# sortirovka.net
KiCad netlist of a schematic drawn in EAGLE
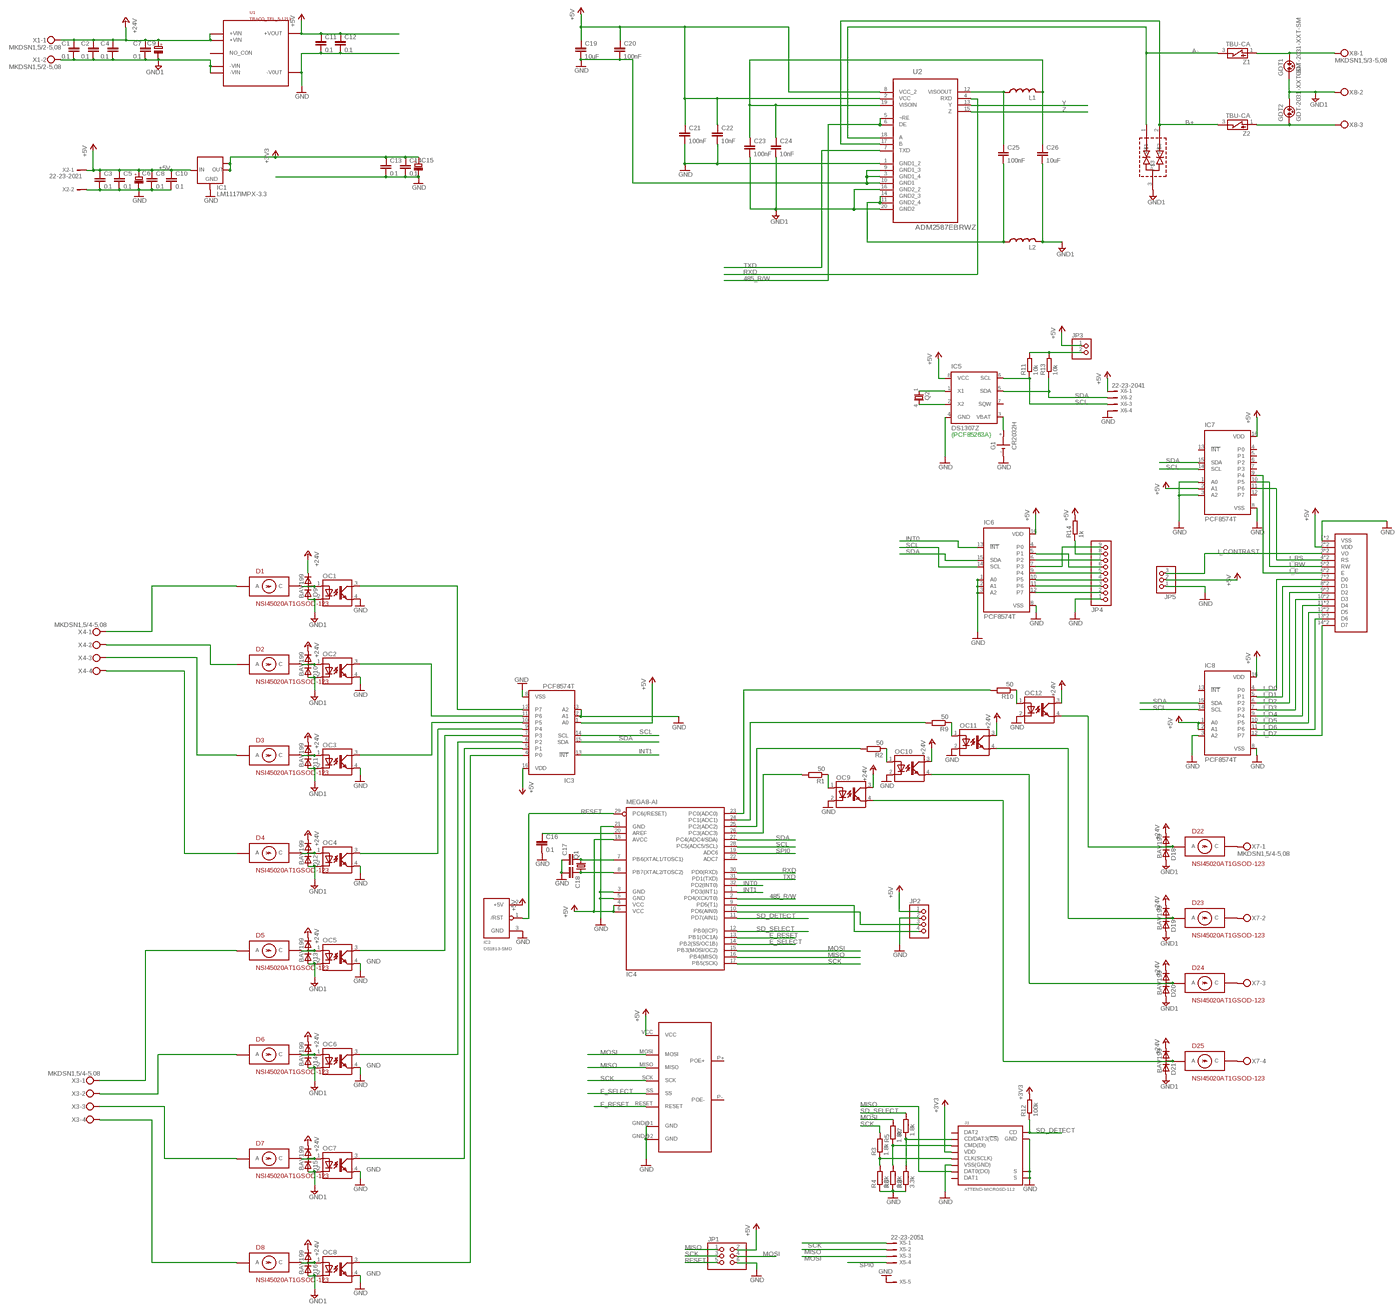
[diagram p0: schematic, sheet 1, overview]
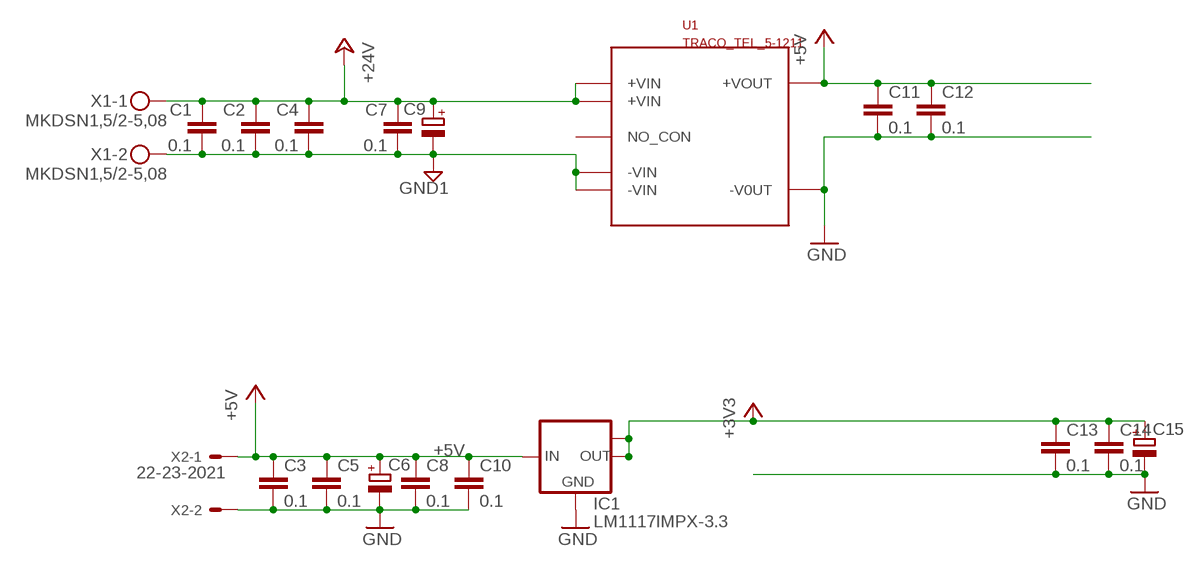
[diagram p1: schematic, sheet 1, part 1 of 4]
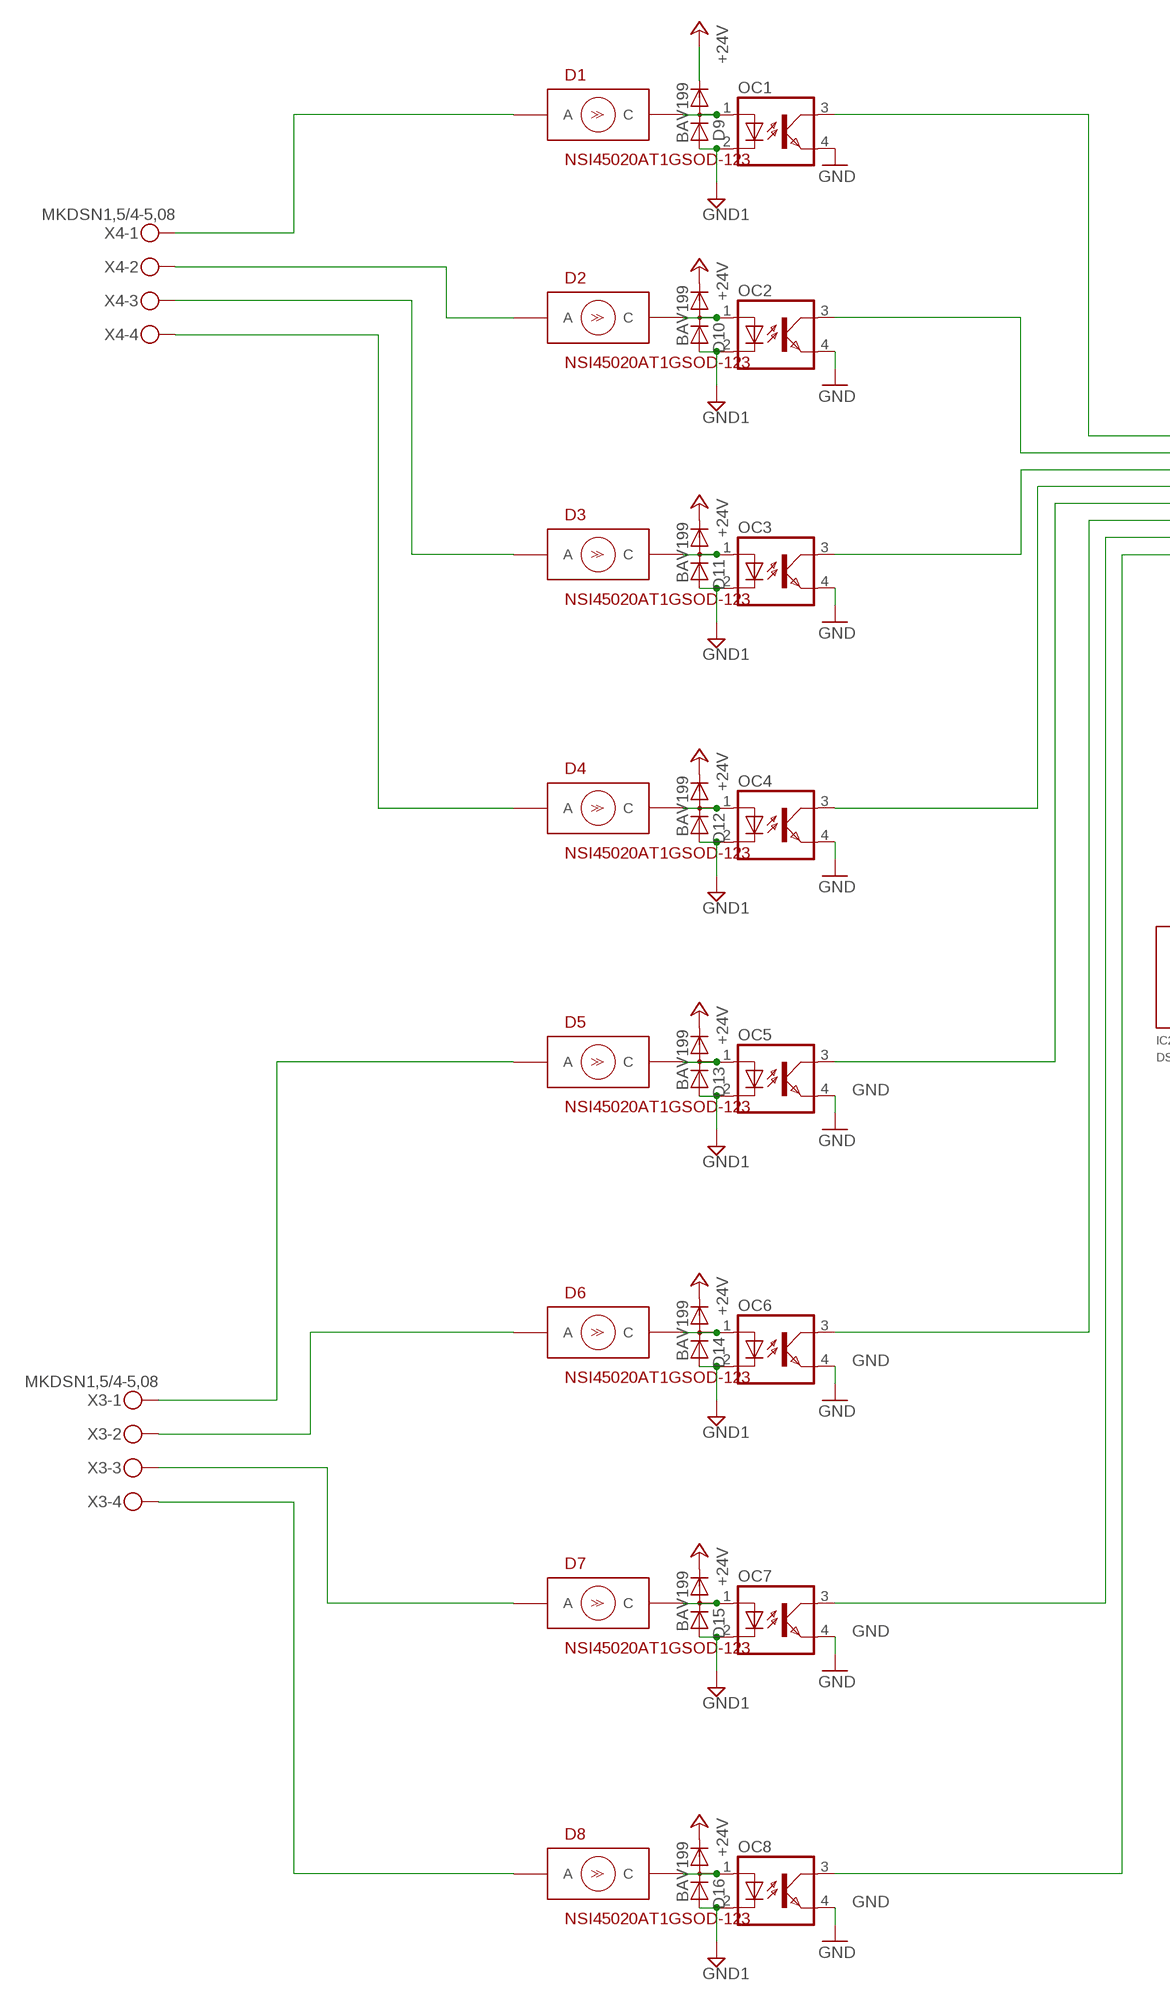
[diagram p2: schematic, sheet 1, part 2 of 4]
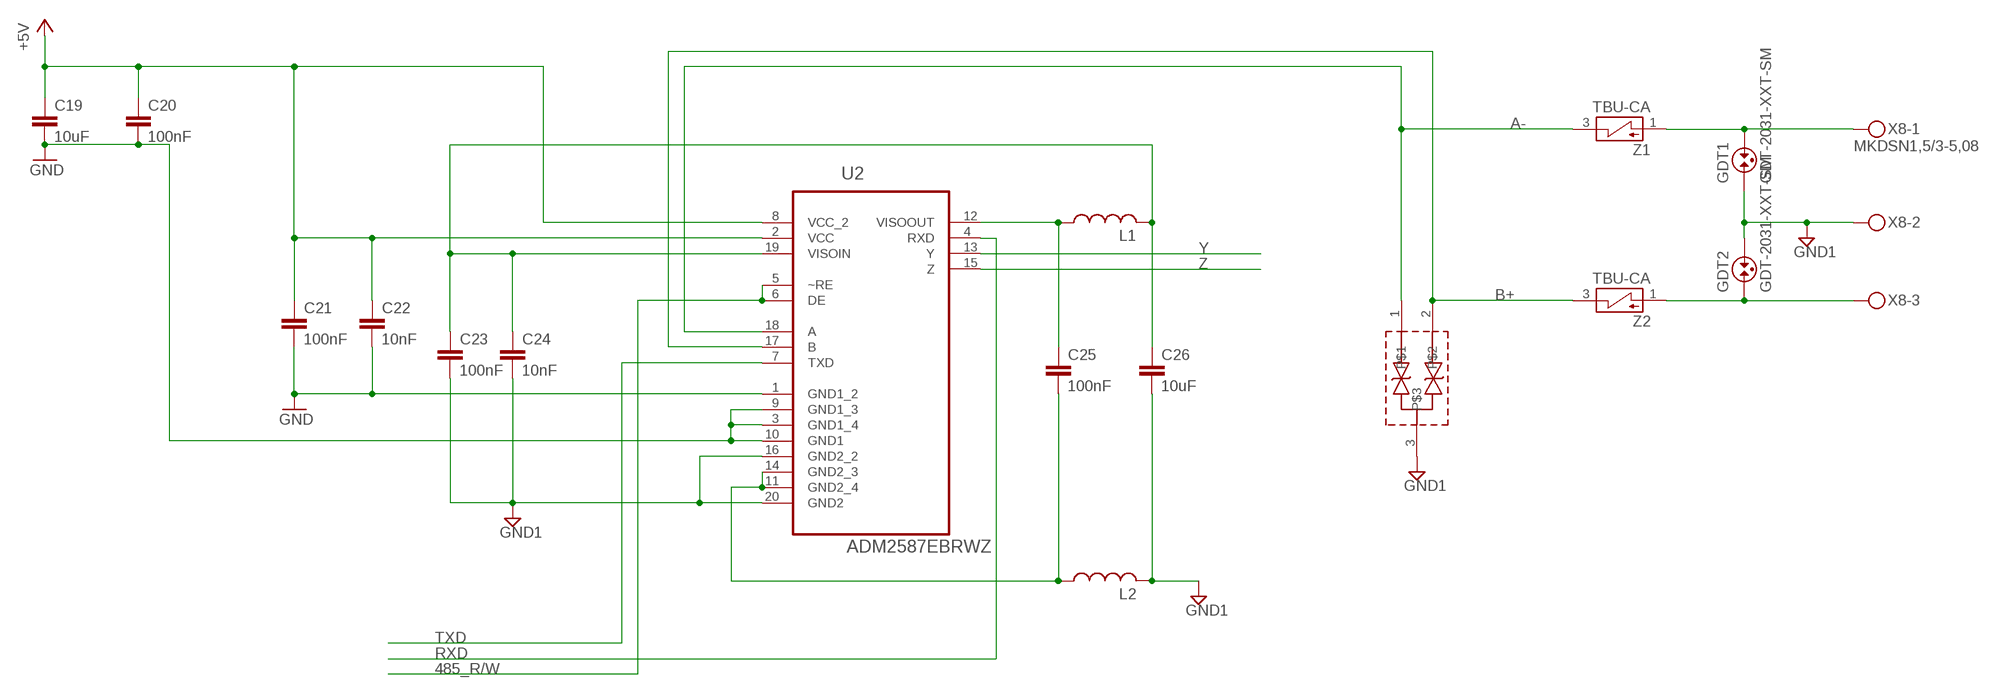
[diagram p3: schematic, sheet 1, part 3 of 4]
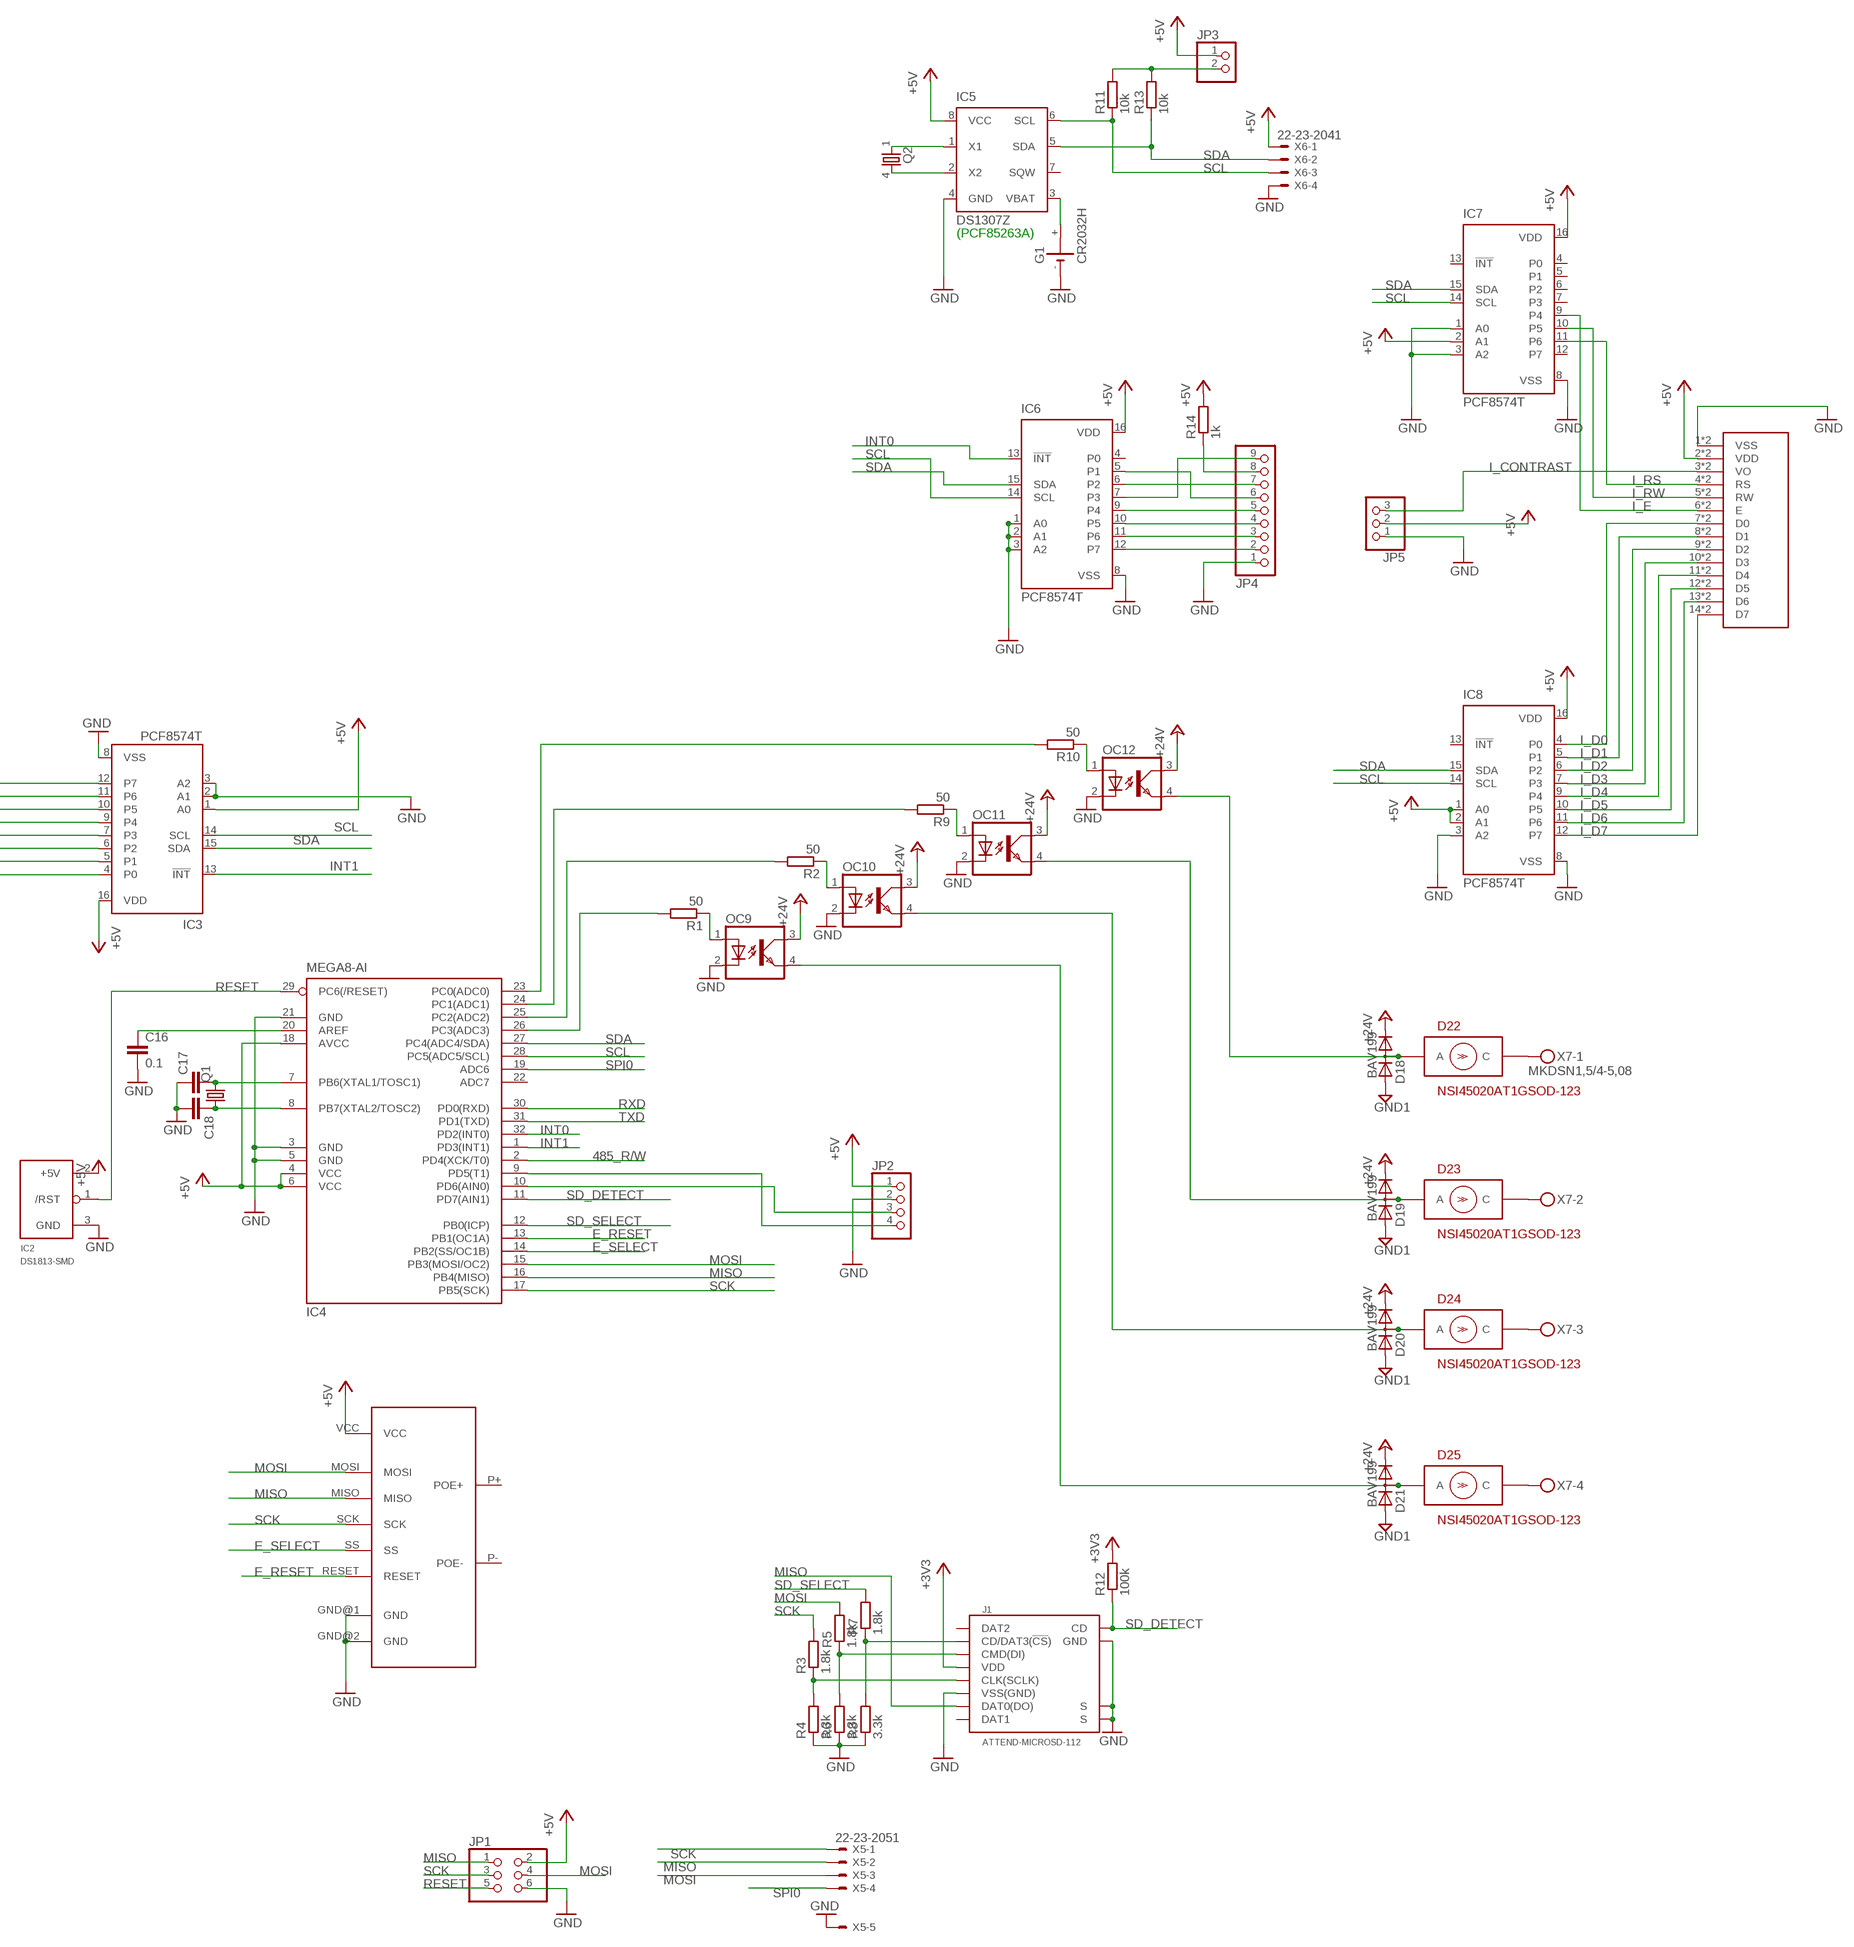
[diagram p4: schematic, sheet 1, part 4 of 4]

(export (version "E")
  (design (tool "Eeschema 10.0.6"))
  (components
    (comp (ref "C1")
      (value "0.1")
      (footprint "eagle-import:C0805")
      (libsource (lib "eagle-import") (part "C-EUC0805"))
    )
    (comp (ref "C2")
      (value "0.1")
      (footprint "eagle-import:C0805")
      (libsource (lib "eagle-import") (part "C-EUC0805"))
    )
    (comp (ref "C3")
      (value "0.1")
      (footprint "eagle-import:C0805")
      (libsource (lib "eagle-import") (part "C-EUC0805"))
    )
    (comp (ref "C4")
      (value "0.1")
      (footprint "eagle-import:C0805")
      (libsource (lib "eagle-import") (part "C-EUC0805"))
    )
    (comp (ref "C5")
      (value "0.1")
      (footprint "eagle-import:C0805")
      (libsource (lib "eagle-import") (part "C-EUC0805"))
    )
    (comp (ref "C6")
      (value "CPOL-EU153CLV-0605")
      (footprint "eagle-import:153CLV-0605")
      (libsource (lib "eagle-import") (part "CPOL-EU153CLV-0605"))
    )
    (comp (ref "C7")
      (value "0.1")
      (footprint "eagle-import:C0805")
      (libsource (lib "eagle-import") (part "C-EUC0805"))
    )
    (comp (ref "C8")
      (value "0.1")
      (footprint "eagle-import:C0805")
      (libsource (lib "eagle-import") (part "C-EUC0805"))
    )
    (comp (ref "C9")
      (value "CPOL-EU153CLV-0605")
      (footprint "eagle-import:153CLV-0605")
      (libsource (lib "eagle-import") (part "CPOL-EU153CLV-0605"))
    )
    (comp (ref "C10")
      (value "0.1")
      (footprint "eagle-import:C0805")
      (libsource (lib "eagle-import") (part "C-EUC0805"))
    )
    (comp (ref "C11")
      (value "0.1")
      (footprint "eagle-import:C0805")
      (libsource (lib "eagle-import") (part "C-EUC0805"))
    )
    (comp (ref "C12")
      (value "0.1")
      (footprint "eagle-import:C0805")
      (libsource (lib "eagle-import") (part "C-EUC0805"))
    )
    (comp (ref "C13")
      (value "0.1")
      (footprint "eagle-import:C0805")
      (libsource (lib "eagle-import") (part "C-EUC0805"))
    )
    (comp (ref "C14")
      (value "0.1")
      (footprint "eagle-import:C0805")
      (libsource (lib "eagle-import") (part "C-EUC0805"))
    )
    (comp (ref "C15")
      (value "CPOL-EU153CLV-0605")
      (footprint "eagle-import:153CLV-0605")
      (libsource (lib "eagle-import") (part "CPOL-EU153CLV-0605"))
    )
    (comp (ref "C16")
      (value "0.1")
      (footprint "eagle-import:C0805")
      (libsource (lib "eagle-import") (part "C-EUC0805"))
    )
    (comp (ref "C17")
      (value "C-EUC0805")
      (footprint "eagle-import:C0805")
      (libsource (lib "eagle-import") (part "C-EUC0805"))
    )
    (comp (ref "C18")
      (value "C-EUC0805")
      (footprint "eagle-import:C0805")
      (libsource (lib "eagle-import") (part "C-EUC0805"))
    )
    (comp (ref "C19")
      (value "10uF")
      (footprint "eagle-import:C0805")
      (libsource (lib "eagle-import") (part "C-EUC0805"))
    )
    (comp (ref "C20")
      (value "100nF")
      (footprint "eagle-import:C0805")
      (libsource (lib "eagle-import") (part "C-EUC0805"))
    )
    (comp (ref "C21")
      (value "100nF")
      (footprint "eagle-import:C0805")
      (libsource (lib "eagle-import") (part "C-EUC0805"))
    )
    (comp (ref "C22")
      (value "10nF")
      (footprint "eagle-import:C0805")
      (libsource (lib "eagle-import") (part "C-EUC0805"))
    )
    (comp (ref "C23")
      (value "100nF")
      (footprint "eagle-import:C0805")
      (libsource (lib "eagle-import") (part "C-EUC0805"))
    )
    (comp (ref "C24")
      (value "10nF")
      (footprint "eagle-import:C0805")
      (libsource (lib "eagle-import") (part "C-EUC0805"))
    )
    (comp (ref "C25")
      (value "100nF")
      (footprint "eagle-import:C0805")
      (libsource (lib "eagle-import") (part "C-EUC0805"))
    )
    (comp (ref "C26")
      (value "10uF")
      (footprint "eagle-import:C0805")
      (libsource (lib "eagle-import") (part "C-EUC0805"))
    )
    (comp (ref "D1")
      (value "NSI45020AT1GSOD-123")
      (footprint "eagle-import:SOD123")
      (libsource (lib "eagle-import") (part "NSI45020AT1GSOD-123"))
    )
    (comp (ref "D2")
      (value "NSI45020AT1GSOD-123")
      (footprint "eagle-import:SOD123")
      (libsource (lib "eagle-import") (part "NSI45020AT1GSOD-123"))
    )
    (comp (ref "D3")
      (value "NSI45020AT1GSOD-123")
      (footprint "eagle-import:SOD123")
      (libsource (lib "eagle-import") (part "NSI45020AT1GSOD-123"))
    )
    (comp (ref "D4")
      (value "NSI45020AT1GSOD-123")
      (footprint "eagle-import:SOD123")
      (libsource (lib "eagle-import") (part "NSI45020AT1GSOD-123"))
    )
    (comp (ref "D5")
      (value "NSI45020AT1GSOD-123")
      (footprint "eagle-import:SOD123")
      (libsource (lib "eagle-import") (part "NSI45020AT1GSOD-123"))
    )
    (comp (ref "D6")
      (value "NSI45020AT1GSOD-123")
      (footprint "eagle-import:SOD123")
      (libsource (lib "eagle-import") (part "NSI45020AT1GSOD-123"))
    )
    (comp (ref "D7")
      (value "NSI45020AT1GSOD-123")
      (footprint "eagle-import:SOD123")
      (libsource (lib "eagle-import") (part "NSI45020AT1GSOD-123"))
    )
    (comp (ref "D8")
      (value "NSI45020AT1GSOD-123")
      (footprint "eagle-import:SOD123")
      (libsource (lib "eagle-import") (part "NSI45020AT1GSOD-123"))
    )
    (comp (ref "D9")
      (value "BAV199")
      (footprint "eagle-import:SOT23")
      (libsource (lib "eagle-import") (part "BAV199"))
    )
    (comp (ref "D10")
      (value "BAV199")
      (footprint "eagle-import:SOT23")
      (libsource (lib "eagle-import") (part "BAV199"))
    )
    (comp (ref "D11")
      (value "BAV199")
      (footprint "eagle-import:SOT23")
      (libsource (lib "eagle-import") (part "BAV199"))
    )
    (comp (ref "D12")
      (value "BAV199")
      (footprint "eagle-import:SOT23")
      (libsource (lib "eagle-import") (part "BAV199"))
    )
    (comp (ref "D13")
      (value "BAV199")
      (footprint "eagle-import:SOT23")
      (libsource (lib "eagle-import") (part "BAV199"))
    )
    (comp (ref "D14")
      (value "BAV199")
      (footprint "eagle-import:SOT23")
      (libsource (lib "eagle-import") (part "BAV199"))
    )
    (comp (ref "D15")
      (value "BAV199")
      (footprint "eagle-import:SOT23")
      (libsource (lib "eagle-import") (part "BAV199"))
    )
    (comp (ref "D16")
      (value "BAV199")
      (footprint "eagle-import:SOT23")
      (libsource (lib "eagle-import") (part "BAV199"))
    )
    (comp (ref "D17")
      (value "CDSOT23-SM712SOT23-R")
      (footprint "eagle-import:SOT23-R")
      (libsource (lib "eagle-import") (part "CDSOT23-SM712SOT23-R"))
    )
    (comp (ref "D18")
      (value "BAV199")
      (footprint "eagle-import:SOT23")
      (libsource (lib "eagle-import") (part "BAV199"))
    )
    (comp (ref "D19")
      (value "BAV199")
      (footprint "eagle-import:SOT23")
      (libsource (lib "eagle-import") (part "BAV199"))
    )
    (comp (ref "D20")
      (value "BAV199")
      (footprint "eagle-import:SOT23")
      (libsource (lib "eagle-import") (part "BAV199"))
    )
    (comp (ref "D21")
      (value "BAV199")
      (footprint "eagle-import:SOT23")
      (libsource (lib "eagle-import") (part "BAV199"))
    )
    (comp (ref "D22")
      (value "NSI45020AT1GSOD-123")
      (footprint "eagle-import:SOD123")
      (libsource (lib "eagle-import") (part "NSI45020AT1GSOD-123"))
    )
    (comp (ref "D23")
      (value "NSI45020AT1GSOD-123")
      (footprint "eagle-import:SOD123")
      (libsource (lib "eagle-import") (part "NSI45020AT1GSOD-123"))
    )
    (comp (ref "D24")
      (value "NSI45020AT1GSOD-123")
      (footprint "eagle-import:SOD123")
      (libsource (lib "eagle-import") (part "NSI45020AT1GSOD-123"))
    )
    (comp (ref "D25")
      (value "NSI45020AT1GSOD-123")
      (footprint "eagle-import:SOD123")
      (libsource (lib "eagle-import") (part "NSI45020AT1GSOD-123"))
    )
    (comp (ref "G1")
      (value "CR2032H")
      (footprint "eagle-import:CR2032H")
      (libsource (lib "eagle-import") (part "CR2032H"))
    )
    (comp (ref "GDT1")
      (value "GDT-2031-XXT-SM")
      (footprint "eagle-import:2031-XXT-SM")
      (libsource (lib "eagle-import") (part "GDT-2031-XXT-SM"))
    )
    (comp (ref "GDT2")
      (value "GDT-2031-XXT-SM")
      (footprint "eagle-import:2031-XXT-SM")
      (libsource (lib "eagle-import") (part "GDT-2031-XXT-SM"))
    )
    (comp (ref "IC1")
      (value "LM1117IMPX-3.3")
      (footprint "eagle-import:SOT223")
      (libsource (lib "eagle-import") (part "LM1117IMPX-3.3"))
    )
    (comp (ref "IC2")
      (value "DS1813-SMD")
      (footprint "eagle-import:SOT-23")
      (libsource (lib "eagle-import") (part "DS1813-SMD"))
    )
    (comp (ref "IC3")
      (value "PCF8574T")
      (footprint "eagle-import:SO16W")
      (fields (field (name "MPN") "PCF8574T/3,512"))
      (libsource (lib "eagle-import") (part "PCF8574T"))
    )
    (comp (ref "IC4")
      (value "MEGA8-AI")
      (footprint "eagle-import:TQFP32-08")
      (fields (field (name "MPN") "ATMEGA8-16AU"))
      (libsource (lib "eagle-import") (part "MEGA8-AI"))
    )
    (comp (ref "IC5")
      (value "DS1307Z")
      (footprint "eagle-import:SOIC8")
      (libsource (lib "eagle-import") (part "DS1307Z"))
    )
    (comp (ref "IC6")
      (value "PCF8574T")
      (footprint "eagle-import:SO16W")
      (fields (field (name "MPN") "PCF8574T/3,512"))
      (libsource (lib "eagle-import") (part "PCF8574T"))
    )
    (comp (ref "IC7")
      (value "PCF8574T")
      (footprint "eagle-import:SO16W")
      (fields (field (name "MPN") "PCF8574T/3,512"))
      (libsource (lib "eagle-import") (part "PCF8574T"))
    )
    (comp (ref "IC8")
      (value "PCF8574T")
      (footprint "eagle-import:SO16W")
      (fields (field (name "MPN") "PCF8574T/3,512"))
      (libsource (lib "eagle-import") (part "PCF8574T"))
    )
    (comp (ref "J1")
      (value "ATTEND-MICROSD-112")
      (footprint "eagle-import:ATTEND-112")
      (libsource (lib "eagle-import") (part "ATTEND-MICROSD-112"))
    )
    (comp (ref "JP1")
      (value "PINHD-2X3")
      (footprint "eagle-import:2X03")
      (libsource (lib "eagle-import") (part "PINHD-2X3"))
    )
    (comp (ref "JP2")
      (value "PINHD-1X4")
      (footprint "eagle-import:1X04")
      (libsource (lib "eagle-import") (part "PINHD-1X4"))
    )
    (comp (ref "JP3")
      (value "PINHD-1X2")
      (footprint "eagle-import:1X02")
      (libsource (lib "eagle-import") (part "PINHD-1X2"))
    )
    (comp (ref "JP4")
      (value "PINHD-1X9")
      (footprint "eagle-import:1X09")
      (libsource (lib "eagle-import") (part "PINHD-1X9"))
    )
    (comp (ref "JP5")
      (value "PINHD-1X3")
      (footprint "eagle-import:1X03")
      (libsource (lib "eagle-import") (part "PINHD-1X3"))
    )
    (comp (ref "L1")
      (value "L-US0402")
      (footprint "eagle-import:L0402")
      (libsource (lib "eagle-import") (part "L-US0402"))
    )
    (comp (ref "L2")
      (value "L-US0402")
      (footprint "eagle-import:L0402")
      (libsource (lib "eagle-import") (part "L-US0402"))
    )
    (comp (ref "LCD1")
      (value "2X16LCDBOTHM162SD07")
      (footprint "eagle-import:2X16LCDBOTH-1")
      (libsource (lib "eagle-import") (part "2X16LCDBOTHM162SD07"))
    )
    (comp (ref "MOD1")
      (value "W5100_MODULESMALL")
      (footprint "eagle-import:W5100_MODULE_1")
      (libsource (lib "eagle-import") (part "W5100_MODULESMALL"))
    )
    (comp (ref "OC1")
      (value "SFH6106REAL")
      (footprint "eagle-import:SFH6106")
      (libsource (lib "eagle-import") (part "SFH6106REAL"))
    )
    (comp (ref "OC2")
      (value "SFH6106REAL")
      (footprint "eagle-import:SFH6106")
      (libsource (lib "eagle-import") (part "SFH6106REAL"))
    )
    (comp (ref "OC3")
      (value "SFH6106REAL")
      (footprint "eagle-import:SFH6106")
      (libsource (lib "eagle-import") (part "SFH6106REAL"))
    )
    (comp (ref "OC4")
      (value "SFH6106REAL")
      (footprint "eagle-import:SFH6106")
      (libsource (lib "eagle-import") (part "SFH6106REAL"))
    )
    (comp (ref "OC5")
      (value "SFH6106REAL")
      (footprint "eagle-import:SFH6106")
      (libsource (lib "eagle-import") (part "SFH6106REAL"))
    )
    (comp (ref "OC6")
      (value "SFH6106REAL")
      (footprint "eagle-import:SFH6106")
      (libsource (lib "eagle-import") (part "SFH6106REAL"))
    )
    (comp (ref "OC7")
      (value "SFH6106REAL")
      (footprint "eagle-import:SFH6106")
      (libsource (lib "eagle-import") (part "SFH6106REAL"))
    )
    (comp (ref "OC8")
      (value "SFH6106REAL")
      (footprint "eagle-import:SFH6106")
      (libsource (lib "eagle-import") (part "SFH6106REAL"))
    )
    (comp (ref "OC9")
      (value "SFH6106REAL")
      (footprint "eagle-import:SFH6106")
      (libsource (lib "eagle-import") (part "SFH6106REAL"))
    )
    (comp (ref "OC10")
      (value "SFH6106REAL")
      (footprint "eagle-import:SFH6106")
      (libsource (lib "eagle-import") (part "SFH6106REAL"))
    )
    (comp (ref "OC11")
      (value "SFH6106REAL")
      (footprint "eagle-import:SFH6106")
      (libsource (lib "eagle-import") (part "SFH6106REAL"))
    )
    (comp (ref "OC12")
      (value "SFH6106REAL")
      (footprint "eagle-import:SFH6106")
      (libsource (lib "eagle-import") (part "SFH6106REAL"))
    )
    (comp (ref "Q1")
      (value "CRYSTALSM49")
      (footprint "eagle-import:SM49")
      (libsource (lib "eagle-import") (part "CRYSTALSM49"))
    )
    (comp (ref "Q2")
      (value "MA306")
      (footprint "eagle-import:MA306")
      (libsource (lib "eagle-import") (part "MA306"))
    )
    (comp (ref "R1")
      (value "50")
      (footprint "eagle-import:R0805")
      (libsource (lib "eagle-import") (part "R-EU_R0805"))
    )
    (comp (ref "R2")
      (value "50")
      (footprint "eagle-import:R0805")
      (libsource (lib "eagle-import") (part "R-EU_R0805"))
    )
    (comp (ref "R3")
      (value "1.8k")
      (footprint "eagle-import:M0805")
      (libsource (lib "eagle-import") (part "R-EU_M0805"))
    )
    (comp (ref "R4")
      (value "3.3k")
      (footprint "eagle-import:M0805")
      (libsource (lib "eagle-import") (part "R-EU_M0805"))
    )
    (comp (ref "R5")
      (value "1.8k")
      (footprint "eagle-import:M0805")
      (libsource (lib "eagle-import") (part "R-EU_M0805"))
    )
    (comp (ref "R6")
      (value "3.3k")
      (footprint "eagle-import:M0805")
      (libsource (lib "eagle-import") (part "R-EU_M0805"))
    )
    (comp (ref "R7")
      (value "1.8k")
      (footprint "eagle-import:M0805")
      (libsource (lib "eagle-import") (part "R-EU_M0805"))
    )
    (comp (ref "R8")
      (value "3.3k")
      (footprint "eagle-import:M0805")
      (libsource (lib "eagle-import") (part "R-EU_M0805"))
    )
    (comp (ref "R9")
      (value "50")
      (footprint "eagle-import:R0805")
      (libsource (lib "eagle-import") (part "R-EU_R0805"))
    )
    (comp (ref "R10")
      (value "50")
      (footprint "eagle-import:R0805")
      (libsource (lib "eagle-import") (part "R-EU_R0805"))
    )
    (comp (ref "R11")
      (value "10k")
      (footprint "eagle-import:R0805")
      (libsource (lib "eagle-import") (part "R-EU_R0805"))
    )
    (comp (ref "R12")
      (value "100k")
      (footprint "eagle-import:M0805")
      (libsource (lib "eagle-import") (part "R-EU_M0805"))
    )
    (comp (ref "R13")
      (value "10k")
      (footprint "eagle-import:R0805")
      (libsource (lib "eagle-import") (part "R-EU_R0805"))
    )
    (comp (ref "R14")
      (value "1k")
      (footprint "eagle-import:R0805")
      (libsource (lib "eagle-import") (part "R-EU_R0805"))
    )
    (comp (ref "U1")
      (value "TRACO_TEL_5-1211")
      (footprint "eagle-import:TRACO_POWER_TL5")
      (libsource (lib "eagle-import") (part "TRACO_TEL_5-1211"))
    )
    (comp (ref "U2")
      (value "ADM2587EBRWZ")
      (footprint "eagle-import:SOIC127P1032X265-20N")
      (libsource (lib "eagle-import") (part "ADM2587EBRWZ"))
    )
    (comp (ref "X1")
      (value "MKDSN1,5/2-5,08")
      (footprint "eagle-import:MKDSN1,5_2-5,08")
      (libsource (lib "eagle-import") (part "MKDSN1,5/2-5,08"))
    )
    (comp (ref "X2")
      (value "22-23-2021")
      (footprint "eagle-import:22-23-2021")
      (fields (field (name "MF") "MOLEX"))
      (libsource (lib "eagle-import") (part "22-23-2021"))
    )
    (comp (ref "X3")
      (value "MKDSN1,5/4-5,08")
      (footprint "eagle-import:MKDSN1,5_4-5,08")
      (libsource (lib "eagle-import") (part "MKDSN1,5/4-5,08"))
    )
    (comp (ref "X4")
      (value "MKDSN1,5/4-5,08")
      (footprint "eagle-import:MKDSN1,5_4-5,08")
      (libsource (lib "eagle-import") (part "MKDSN1,5/4-5,08"))
    )
    (comp (ref "X5")
      (value "22-23-2051")
      (footprint "eagle-import:22-23-2051")
      (fields (field (name "MF") "MOLEX"))
      (libsource (lib "eagle-import") (part "22-23-2051"))
    )
    (comp (ref "X6")
      (value "22-23-2041")
      (footprint "eagle-import:22-23-2041")
      (fields (field (name "MF") "MOLEX"))
      (libsource (lib "eagle-import") (part "22-23-2041"))
    )
    (comp (ref "X7")
      (value "MKDSN1,5/4-5,08")
      (footprint "eagle-import:MKDSN1,5_4-5,08")
      (libsource (lib "eagle-import") (part "MKDSN1,5/4-5,08"))
    )
    (comp (ref "X8")
      (value "MKDSN1,5/3-5,08")
      (footprint "eagle-import:MKDSN1,5_3-5,08")
      (libsource (lib "eagle-import") (part "MKDSN1,5/3-5,08"))
    )
    (comp (ref "Z1")
      (value "TBU-CA")
      (footprint "eagle-import:TBU-CA")
      (libsource (lib "eagle-import") (part "TBU-CA"))
    )
    (comp (ref "Z2")
      (value "TBU-CA")
      (footprint "eagle-import:TBU-CA")
      (libsource (lib "eagle-import") (part "TBU-CA"))
    )
  )
  (nets
    (net (code "1") (name "+3V3") (class "Default")
      (node (ref "C13") (pin "1") (pinfunction "1_1") (pintype "passive"))
      (node (ref "C14") (pin "1") (pinfunction "1_1") (pintype "passive"))
      (node (ref "C15") (pin "+") (pinfunction "+_+") (pintype "passive"))
      (node (ref "IC1") (pin "2") (pinfunction "OUT_2") (pintype "passive"))
      (node (ref "IC1") (pin "TAB") (pinfunction "OUT1_TAB") (pintype "passive"))
      (node (ref "J1") (pin "VDD") (pinfunction "VDD_VDD") (pintype "power_in"))
      (node (ref "R12") (pin "2") (pinfunction "2_2") (pintype "passive"))
    )
    (net (code "2") (name "+5V") (class "Default")
      (node (ref "C10") (pin "1") (pinfunction "1_1") (pintype "passive"))
      (node (ref "C11") (pin "1") (pinfunction "1_1") (pintype "passive"))
      (node (ref "C12") (pin "1") (pinfunction "1_1") (pintype "passive"))
      (node (ref "C19") (pin "1") (pinfunction "1_1") (pintype "passive"))
      (node (ref "C20") (pin "1") (pinfunction "1_1") (pintype "passive"))
      (node (ref "C21") (pin "1") (pinfunction "1_1") (pintype "passive"))
      (node (ref "C22") (pin "1") (pinfunction "1_1") (pintype "passive"))
      (node (ref "C3") (pin "1") (pinfunction "1_1") (pintype "passive"))
      (node (ref "C5") (pin "1") (pinfunction "1_1") (pintype "passive"))
      (node (ref "C6") (pin "+") (pinfunction "+_+") (pintype "passive"))
      (node (ref "C8") (pin "1") (pinfunction "1_1") (pintype "passive"))
      (node (ref "IC1") (pin "3") (pinfunction "IN_3") (pintype "input"))
      (node (ref "IC2") (pin "2") (pinfunction "+5V_2") (pintype "power_in"))
      (node (ref "IC3") (pin "1") (pinfunction "A0_1") (pintype "input"))
      (node (ref "IC3") (pin "16") (pinfunction "VDD_16") (pintype "power_in"))
      (node (ref "IC4") (pin "18") (pinfunction "AVCC_18") (pintype "power_in"))
      (node (ref "IC4") (pin "4") (pinfunction "VCC_4") (pintype "power_in"))
      (node (ref "IC4") (pin "6") (pinfunction "VCC_6") (pintype "power_in"))
      (node (ref "IC5") (pin "8") (pinfunction "VCC_8") (pintype "power_in"))
      (node (ref "IC6") (pin "16") (pinfunction "VDD_16") (pintype "power_in"))
      (node (ref "IC7") (pin "16") (pinfunction "VDD_16") (pintype "power_in"))
      (node (ref "IC7") (pin "2") (pinfunction "A1_2") (pintype "input"))
      (node (ref "IC8") (pin "1") (pinfunction "A0_1") (pintype "input"))
      (node (ref "IC8") (pin "16") (pinfunction "VDD_16") (pintype "power_in"))
      (node (ref "IC8") (pin "2") (pinfunction "A1_2") (pintype "input"))
      (node (ref "JP1") (pin "2") (pinfunction "2_2") (pintype "passive"))
      (node (ref "JP2") (pin "1") (pinfunction "1_1") (pintype "passive"))
      (node (ref "JP3") (pin "1") (pinfunction "1_1") (pintype "passive"))
      (node (ref "JP5") (pin "2") (pinfunction "2_2") (pintype "passive"))
      (node (ref "LCD1") (pin "16") (pinfunction "VDD_16") (pintype "bidirectional"))
      (node (ref "LCD1") (pin "2") (pinfunction "VDD_2") (pintype "bidirectional"))
      (node (ref "MOD1") (pin "VCC") (pinfunction "VCC_VCC") (pintype "bidirectional"))
      (node (ref "R14") (pin "2") (pinfunction "2_2") (pintype "passive"))
      (node (ref "U1") (pin "+VOUT") (pinfunction "+VOUT_+VOUT") (pintype "bidirectional"))
      (node (ref "U2") (pin "2") (pinfunction "VCC_2") (pintype "power_in"))
      (node (ref "U2") (pin "8") (pinfunction "VCC_2_8") (pintype "power_in"))
      (node (ref "X2") (pin "1") (pinfunction "S_1") (pintype "passive"))
      (node (ref "X6") (pin "1") (pinfunction "S_1") (pintype "passive"))
    )
    (net (code "3") (name "+24V") (class "Default")
      (node (ref "C1") (pin "1") (pinfunction "1_1") (pintype "passive"))
      (node (ref "C2") (pin "1") (pinfunction "1_1") (pintype "passive"))
      (node (ref "C4") (pin "1") (pinfunction "1_1") (pintype "passive"))
      (node (ref "C7") (pin "1") (pinfunction "1_1") (pintype "passive"))
      (node (ref "C9") (pin "+") (pinfunction "+_+") (pintype "passive"))
      (node (ref "D10") (pin "2") (pinfunction "C_2") (pintype "passive"))
      (node (ref "D11") (pin "2") (pinfunction "C_2") (pintype "passive"))
      (node (ref "D12") (pin "2") (pinfunction "C_2") (pintype "passive"))
      (node (ref "D13") (pin "2") (pinfunction "C_2") (pintype "passive"))
      (node (ref "D14") (pin "2") (pinfunction "C_2") (pintype "passive"))
      (node (ref "D15") (pin "2") (pinfunction "C_2") (pintype "passive"))
      (node (ref "D16") (pin "2") (pinfunction "C_2") (pintype "passive"))
      (node (ref "D18") (pin "2") (pinfunction "C_2") (pintype "passive"))
      (node (ref "D19") (pin "2") (pinfunction "C_2") (pintype "passive"))
      (node (ref "D20") (pin "2") (pinfunction "C_2") (pintype "passive"))
      (node (ref "D21") (pin "2") (pinfunction "C_2") (pintype "passive"))
      (node (ref "D9") (pin "2") (pinfunction "C_2") (pintype "passive"))
      (node (ref "OC10") (pin "3") (pinfunction "COL_3") (pintype "passive"))
      (node (ref "OC11") (pin "3") (pinfunction "COL_3") (pintype "passive"))
      (node (ref "OC12") (pin "3") (pinfunction "COL_3") (pintype "passive"))
      (node (ref "OC9") (pin "3") (pinfunction "COL_3") (pintype "passive"))
      (node (ref "U1") (pin "+VIN@1") (pinfunction "+VIN_+VIN@1") (pintype "bidirectional"))
      (node (ref "U1") (pin "+VIN@2") (pinfunction "+VIN_+VIN@2") (pintype "bidirectional"))
      (node (ref "X1") (pin "1") (pinfunction "KL_1") (pintype "passive"))
    )
    (net (code "4") (name "/485_R{slash}W") (class "Default")
      (node (ref "IC4") (pin "2") (pinfunction "PD4(XCK/T0)_2") (pintype "bidirectional"))
      (node (ref "U2") (pin "5") (pinfunction "~{RE}_5") (pintype "input"))
      (node (ref "U2") (pin "6") (pinfunction "DE_6") (pintype "input"))
    )
    (net (code "5") (name "/A-") (class "Default")
      (node (ref "D17") (pin "1") (pinfunction "P$1_1") (pintype "bidirectional"))
      (node (ref "U2") (pin "18") (pinfunction "A_18") (pintype "input"))
      (node (ref "Z1") (pin "3") (pinfunction "2_3") (pintype "passive"))
    )
    (net (code "6") (name "/B+") (class "Default")
      (node (ref "D17") (pin "2") (pinfunction "P$2_2") (pintype "bidirectional"))
      (node (ref "U2") (pin "17") (pinfunction "B_17") (pintype "input"))
      (node (ref "Z2") (pin "3") (pinfunction "2_3") (pintype "passive"))
    )
    (net (code "7") (name "/E_RESET") (class "Default")
      (node (ref "IC4") (pin "13") (pinfunction "PB1(OC1A)_13") (pintype "bidirectional"))
      (node (ref "MOD1") (pin "RESET") (pinfunction "RESET_RESET") (pintype "bidirectional"))
    )
    (net (code "8") (name "/E_SELECT") (class "Default")
      (node (ref "IC4") (pin "14") (pinfunction "PB2(SS/OC1B)_14") (pintype "bidirectional"))
      (node (ref "MOD1") (pin "SS") (pinfunction "SS_SS") (pintype "bidirectional"))
    )
    (net (code "9") (name "/INT0") (class "Default")
      (node (ref "IC4") (pin "32") (pinfunction "PD2(INT0)_32") (pintype "bidirectional"))
      (node (ref "IC6") (pin "13") (pinfunction "~{INT}_13") (pintype "output"))
    )
    (net (code "10") (name "/INT1") (class "Default")
      (node (ref "IC3") (pin "13") (pinfunction "~{INT}_13") (pintype "output"))
      (node (ref "IC4") (pin "1") (pinfunction "PD3(INT1)_1") (pintype "bidirectional"))
    )
    (net (code "11") (name "/I_CONTRAST") (class "Default")
      (node (ref "JP5") (pin "3") (pinfunction "3_3") (pintype "passive"))
      (node (ref "LCD1") (pin "17") (pinfunction "VO_17") (pintype "bidirectional"))
      (node (ref "LCD1") (pin "3") (pinfunction "VO_3") (pintype "bidirectional"))
    )
    (net (code "12") (name "/I_D0") (class "Default")
      (node (ref "IC8") (pin "4") (pinfunction "P0_4") (pintype "bidirectional"))
      (node (ref "LCD1") (pin "21") (pinfunction "D0_21") (pintype "bidirectional"))
      (node (ref "LCD1") (pin "7") (pinfunction "D0_7") (pintype "bidirectional"))
    )
    (net (code "13") (name "/I_D1") (class "Default")
      (node (ref "IC8") (pin "5") (pinfunction "P1_5") (pintype "bidirectional"))
      (node (ref "LCD1") (pin "22") (pinfunction "D1_22") (pintype "bidirectional"))
      (node (ref "LCD1") (pin "8") (pinfunction "D1_8") (pintype "bidirectional"))
    )
    (net (code "14") (name "/I_D2") (class "Default")
      (node (ref "IC8") (pin "6") (pinfunction "P2_6") (pintype "bidirectional"))
      (node (ref "LCD1") (pin "23") (pinfunction "D2_23") (pintype "bidirectional"))
      (node (ref "LCD1") (pin "9") (pinfunction "D2_9") (pintype "bidirectional"))
    )
    (net (code "15") (name "/I_D3") (class "Default")
      (node (ref "IC8") (pin "7") (pinfunction "P3_7") (pintype "bidirectional"))
      (node (ref "LCD1") (pin "10") (pinfunction "D3_10") (pintype "bidirectional"))
      (node (ref "LCD1") (pin "24") (pinfunction "D3_24") (pintype "bidirectional"))
    )
    (net (code "16") (name "/I_D4") (class "Default")
      (node (ref "IC8") (pin "9") (pinfunction "P4_9") (pintype "bidirectional"))
      (node (ref "LCD1") (pin "11") (pinfunction "D4_11") (pintype "bidirectional"))
      (node (ref "LCD1") (pin "25") (pinfunction "D4_25") (pintype "bidirectional"))
    )
    (net (code "17") (name "/I_D5") (class "Default")
      (node (ref "IC8") (pin "10") (pinfunction "P5_10") (pintype "bidirectional"))
      (node (ref "LCD1") (pin "12") (pinfunction "D5_12") (pintype "bidirectional"))
      (node (ref "LCD1") (pin "26") (pinfunction "D5_26") (pintype "bidirectional"))
    )
    (net (code "18") (name "/I_D6") (class "Default")
      (node (ref "IC8") (pin "11") (pinfunction "P6_11") (pintype "bidirectional"))
      (node (ref "LCD1") (pin "13") (pinfunction "D6_13") (pintype "bidirectional"))
      (node (ref "LCD1") (pin "27") (pinfunction "D6_27") (pintype "bidirectional"))
    )
    (net (code "19") (name "/I_D7") (class "Default")
      (node (ref "IC8") (pin "12") (pinfunction "P7_12") (pintype "bidirectional"))
      (node (ref "LCD1") (pin "14") (pinfunction "D7_14") (pintype "bidirectional"))
      (node (ref "LCD1") (pin "28") (pinfunction "D7_28") (pintype "bidirectional"))
    )
    (net (code "20") (name "/I_E") (class "Default")
      (node (ref "IC7") (pin "9") (pinfunction "P4_9") (pintype "bidirectional"))
      (node (ref "LCD1") (pin "20") (pinfunction "E_20") (pintype "bidirectional"))
      (node (ref "LCD1") (pin "6") (pinfunction "E_6") (pintype "bidirectional"))
    )
    (net (code "21") (name "/I_RS") (class "Default")
      (node (ref "IC7") (pin "11") (pinfunction "P6_11") (pintype "bidirectional"))
      (node (ref "LCD1") (pin "18") (pinfunction "RS_18") (pintype "bidirectional"))
      (node (ref "LCD1") (pin "4") (pinfunction "RS_4") (pintype "bidirectional"))
    )
    (net (code "22") (name "/I_RW") (class "Default")
      (node (ref "IC7") (pin "10") (pinfunction "P5_10") (pintype "bidirectional"))
      (node (ref "LCD1") (pin "19") (pinfunction "RW_19") (pintype "bidirectional"))
      (node (ref "LCD1") (pin "5") (pinfunction "RW_5") (pintype "bidirectional"))
    )
    (net (code "23") (name "/MISO") (class "Default")
      (node (ref "IC4") (pin "16") (pinfunction "PB4(MISO)_16") (pintype "bidirectional"))
      (node (ref "J1") (pin "DAT0") (pinfunction "DAT0(DO)_DAT0") (pintype "bidirectional"))
      (node (ref "JP1") (pin "1") (pinfunction "1_1") (pintype "passive"))
      (node (ref "MOD1") (pin "MISO") (pinfunction "MISO_MISO") (pintype "bidirectional"))
      (node (ref "X5") (pin "2") (pinfunction "S_2") (pintype "passive"))
    )
    (net (code "24") (name "/MOSI") (class "Default")
      (node (ref "IC4") (pin "15") (pinfunction "PB3(MOSI/OC2)_15") (pintype "bidirectional"))
      (node (ref "JP1") (pin "4") (pinfunction "4_4") (pintype "passive"))
      (node (ref "MOD1") (pin "MOSI") (pinfunction "MOSI_MOSI") (pintype "bidirectional"))
      (node (ref "R5") (pin "2") (pinfunction "2_2") (pintype "passive"))
      (node (ref "X5") (pin "3") (pinfunction "S_3") (pintype "passive"))
    )
    (net (code "25") (name "/RESET") (class "Default")
      (node (ref "IC2") (pin "1") (pinfunction "/RST_1") (pintype "passive"))
      (node (ref "IC4") (pin "29") (pinfunction "PC6(/RESET)_29") (pintype "bidirectional"))
      (node (ref "JP1") (pin "5") (pinfunction "5_5") (pintype "passive"))
    )
    (net (code "26") (name "/RXD") (class "Default")
      (node (ref "IC4") (pin "30") (pinfunction "PD0(RXD)_30") (pintype "bidirectional"))
      (node (ref "U2") (pin "4") (pinfunction "RXD_4") (pintype "output"))
    )
    (net (code "27") (name "/SCK") (class "Default")
      (node (ref "IC4") (pin "17") (pinfunction "PB5(SCK)_17") (pintype "bidirectional"))
      (node (ref "JP1") (pin "3") (pinfunction "3_3") (pintype "passive"))
      (node (ref "MOD1") (pin "SCK") (pinfunction "SCK_SCK") (pintype "bidirectional"))
      (node (ref "R3") (pin "2") (pinfunction "2_2") (pintype "passive"))
      (node (ref "X5") (pin "1") (pinfunction "S_1") (pintype "passive"))
    )
    (net (code "28") (name "/SCL") (class "Default")
      (node (ref "IC3") (pin "14") (pinfunction "SCL_14") (pintype "input"))
      (node (ref "IC4") (pin "28") (pinfunction "PC5(ADC5/SCL)_28") (pintype "bidirectional"))
      (node (ref "IC5") (pin "6") (pinfunction "SCL_6") (pintype "input"))
      (node (ref "IC6") (pin "14") (pinfunction "SCL_14") (pintype "input"))
      (node (ref "IC7") (pin "14") (pinfunction "SCL_14") (pintype "input"))
      (node (ref "IC8") (pin "14") (pinfunction "SCL_14") (pintype "input"))
      (node (ref "R11") (pin "1") (pinfunction "1_1") (pintype "passive"))
      (node (ref "X6") (pin "3") (pinfunction "S_3") (pintype "passive"))
    )
    (net (code "29") (name "/SDA") (class "Default")
      (node (ref "IC3") (pin "15") (pinfunction "SDA_15") (pintype "bidirectional"))
      (node (ref "IC4") (pin "27") (pinfunction "PC4(ADC4/SDA)_27") (pintype "bidirectional"))
      (node (ref "IC5") (pin "5") (pinfunction "SDA_5") (pintype "bidirectional"))
      (node (ref "IC6") (pin "15") (pinfunction "SDA_15") (pintype "bidirectional"))
      (node (ref "IC7") (pin "15") (pinfunction "SDA_15") (pintype "bidirectional"))
      (node (ref "IC8") (pin "15") (pinfunction "SDA_15") (pintype "bidirectional"))
      (node (ref "R13") (pin "1") (pinfunction "1_1") (pintype "passive"))
      (node (ref "X6") (pin "2") (pinfunction "S_2") (pintype "passive"))
    )
    (net (code "30") (name "/SD_DETECT") (class "Default")
      (node (ref "IC4") (pin "11") (pinfunction "PD7(AIN1)_11") (pintype "bidirectional"))
      (node (ref "J1") (pin "CD") (pinfunction "CD_CD") (pintype "open_collector"))
      (node (ref "R12") (pin "1") (pinfunction "1_1") (pintype "passive"))
    )
    (net (code "31") (name "/SD_SELECT") (class "Default")
      (node (ref "IC4") (pin "12") (pinfunction "PB0(ICP)_12") (pintype "bidirectional"))
      (node (ref "R7") (pin "2") (pinfunction "2_2") (pintype "passive"))
    )
    (net (code "32") (name "/SPI0") (class "Default")
      (node (ref "IC4") (pin "19") (pinfunction "ADC6_19") (pintype "bidirectional"))
      (node (ref "X5") (pin "4") (pinfunction "S_4") (pintype "passive"))
    )
    (net (code "33") (name "/TXD") (class "Default")
      (node (ref "IC4") (pin "31") (pinfunction "PD1(TXD)_31") (pintype "bidirectional"))
      (node (ref "U2") (pin "7") (pinfunction "TXD_7") (pintype "input"))
    )
    (net (code "34") (name "/Y") (class "Default")
      (node (ref "U2") (pin "13") (pinfunction "Y_13") (pintype "output"))
    )
    (net (code "35") (name "/Z") (class "Default")
      (node (ref "U2") (pin "15") (pinfunction "Z_15") (pintype "output"))
    )
    (net (code "36") (name "GND") (class "Default")
      (node (ref "C10") (pin "2") (pinfunction "2_2") (pintype "passive"))
      (node (ref "C11") (pin "2") (pinfunction "2_2") (pintype "passive"))
      (node (ref "C12") (pin "2") (pinfunction "2_2") (pintype "passive"))
      (node (ref "C13") (pin "2") (pinfunction "2_2") (pintype "passive"))
      (node (ref "C14") (pin "2") (pinfunction "2_2") (pintype "passive"))
      (node (ref "C15") (pin "-") (pinfunction "-_-") (pintype "passive"))
      (node (ref "C16") (pin "2") (pinfunction "2_2") (pintype "passive"))
      (node (ref "C17") (pin "1") (pinfunction "1_1") (pintype "passive"))
      (node (ref "C18") (pin "2") (pinfunction "2_2") (pintype "passive"))
      (node (ref "C19") (pin "2") (pinfunction "2_2") (pintype "passive"))
      (node (ref "C20") (pin "2") (pinfunction "2_2") (pintype "passive"))
      (node (ref "C21") (pin "2") (pinfunction "2_2") (pintype "passive"))
      (node (ref "C22") (pin "2") (pinfunction "2_2") (pintype "passive"))
      (node (ref "C3") (pin "2") (pinfunction "2_2") (pintype "passive"))
      (node (ref "C5") (pin "2") (pinfunction "2_2") (pintype "passive"))
      (node (ref "C6") (pin "-") (pinfunction "-_-") (pintype "passive"))
      (node (ref "C8") (pin "2") (pinfunction "2_2") (pintype "passive"))
      (node (ref "G1") (pin "-") (pinfunction "-_-") (pintype "passive"))
      (node (ref "IC1") (pin "1") (pinfunction "GND_1") (pintype "input"))
      (node (ref "IC2") (pin "3") (pinfunction "GND_3") (pintype "power_in"))
      (node (ref "IC3") (pin "2") (pinfunction "A1_2") (pintype "input"))
      (node (ref "IC3") (pin "3") (pinfunction "A2_3") (pintype "input"))
      (node (ref "IC3") (pin "8") (pinfunction "VSS_8") (pintype "power_in"))
      (node (ref "IC4") (pin "21") (pinfunction "GND_21") (pintype "power_in"))
      (node (ref "IC4") (pin "3") (pinfunction "GND_3") (pintype "power_in"))
      (node (ref "IC4") (pin "5") (pinfunction "GND_5") (pintype "power_in"))
      (node (ref "IC5") (pin "4") (pinfunction "GND_4") (pintype "power_in"))
      (node (ref "IC6") (pin "1") (pinfunction "A0_1") (pintype "input"))
      (node (ref "IC6") (pin "2") (pinfunction "A1_2") (pintype "input"))
      (node (ref "IC6") (pin "3") (pinfunction "A2_3") (pintype "input"))
      (node (ref "IC6") (pin "8") (pinfunction "VSS_8") (pintype "power_in"))
      (node (ref "IC7") (pin "1") (pinfunction "A0_1") (pintype "input"))
      (node (ref "IC7") (pin "3") (pinfunction "A2_3") (pintype "input"))
      (node (ref "IC7") (pin "8") (pinfunction "VSS_8") (pintype "power_in"))
      (node (ref "IC8") (pin "3") (pinfunction "A2_3") (pintype "input"))
      (node (ref "IC8") (pin "8") (pinfunction "VSS_8") (pintype "power_in"))
      (node (ref "J1") (pin "GND") (pinfunction "GND_GND") (pintype "passive"))
      (node (ref "J1") (pin "S1") (pinfunction "S_S1") (pintype "passive"))
      (node (ref "J1") (pin "S2") (pinfunction "S_S2") (pintype "passive"))
      (node (ref "J1") (pin "VSS") (pinfunction "VSS(GND)_VSS") (pintype "power_in"))
      (node (ref "JP1") (pin "6") (pinfunction "6_6") (pintype "passive"))
      (node (ref "JP2") (pin "2") (pinfunction "2_2") (pintype "passive"))
      (node (ref "JP4") (pin "1") (pinfunction "1_1") (pintype "passive"))
      (node (ref "JP5") (pin "1") (pinfunction "1_1") (pintype "passive"))
      (node (ref "LCD1") (pin "1") (pinfunction "VSS_1") (pintype "bidirectional"))
      (node (ref "LCD1") (pin "15") (pinfunction "VSS_15") (pintype "bidirectional"))
      (node (ref "MOD1") (pin "GND@1") (pinfunction "GND_GND@1") (pintype "bidirectional"))
      (node (ref "MOD1") (pin "GND@2") (pinfunction "GND_GND@2") (pintype "bidirectional"))
      (node (ref "OC1") (pin "4") (pinfunction "EMIT_4") (pintype "passive"))
      (node (ref "OC10") (pin "2") (pinfunction "C_2") (pintype "passive"))
      (node (ref "OC11") (pin "2") (pinfunction "C_2") (pintype "passive"))
      (node (ref "OC12") (pin "2") (pinfunction "C_2") (pintype "passive"))
      (node (ref "OC2") (pin "4") (pinfunction "EMIT_4") (pintype "passive"))
      (node (ref "OC3") (pin "4") (pinfunction "EMIT_4") (pintype "passive"))
      (node (ref "OC4") (pin "4") (pinfunction "EMIT_4") (pintype "passive"))
      (node (ref "OC5") (pin "4") (pinfunction "EMIT_4") (pintype "passive"))
      (node (ref "OC6") (pin "4") (pinfunction "EMIT_4") (pintype "passive"))
      (node (ref "OC7") (pin "4") (pinfunction "EMIT_4") (pintype "passive"))
      (node (ref "OC8") (pin "4") (pinfunction "EMIT_4") (pintype "passive"))
      (node (ref "OC9") (pin "2") (pinfunction "C_2") (pintype "passive"))
      (node (ref "R4") (pin "1") (pinfunction "1_1") (pintype "passive"))
      (node (ref "R6") (pin "1") (pinfunction "1_1") (pintype "passive"))
      (node (ref "R8") (pin "1") (pinfunction "1_1") (pintype "passive"))
      (node (ref "U1") (pin "-VOUT") (pinfunction "-V0UT_-VOUT") (pintype "bidirectional"))
      (node (ref "U2") (pin "1") (pinfunction "GND1_2_1") (pintype "passive"))
      (node (ref "U2") (pin "10") (pinfunction "GND1_10") (pintype "passive"))
      (node (ref "U2") (pin "3") (pinfunction "GND1_4_3") (pintype "passive"))
      (node (ref "U2") (pin "9") (pinfunction "GND1_3_9") (pintype "passive"))
      (node (ref "X2") (pin "2") (pinfunction "S_2") (pintype "passive"))
      (node (ref "X5") (pin "5") (pinfunction "S_5") (pintype "passive"))
      (node (ref "X6") (pin "4") (pinfunction "S_4") (pintype "passive"))
    )
    (net (code "37") (name "GND1") (class "Default")
      (node (ref "C1") (pin "2") (pinfunction "2_2") (pintype "passive"))
      (node (ref "C2") (pin "2") (pinfunction "2_2") (pintype "passive"))
      (node (ref "C23") (pin "2") (pinfunction "2_2") (pintype "passive"))
      (node (ref "C24") (pin "2") (pinfunction "2_2") (pintype "passive"))
      (node (ref "C26") (pin "2") (pinfunction "2_2") (pintype "passive"))
      (node (ref "C4") (pin "2") (pinfunction "2_2") (pintype "passive"))
      (node (ref "C7") (pin "2") (pinfunction "2_2") (pintype "passive"))
      (node (ref "C9") (pin "-") (pinfunction "-_-") (pintype "passive"))
      (node (ref "D10") (pin "1") (pinfunction "A_1") (pintype "passive"))
      (node (ref "D11") (pin "1") (pinfunction "A_1") (pintype "passive"))
      (node (ref "D12") (pin "1") (pinfunction "A_1") (pintype "passive"))
      (node (ref "D13") (pin "1") (pinfunction "A_1") (pintype "passive"))
      (node (ref "D14") (pin "1") (pinfunction "A_1") (pintype "passive"))
      (node (ref "D15") (pin "1") (pinfunction "A_1") (pintype "passive"))
      (node (ref "D16") (pin "1") (pinfunction "A_1") (pintype "passive"))
      (node (ref "D17") (pin "3") (pinfunction "P$3_3") (pintype "bidirectional"))
      (node (ref "D18") (pin "1") (pinfunction "A_1") (pintype "passive"))
      (node (ref "D19") (pin "1") (pinfunction "A_1") (pintype "passive"))
      (node (ref "D20") (pin "1") (pinfunction "A_1") (pintype "passive"))
      (node (ref "D21") (pin "1") (pinfunction "A_1") (pintype "passive"))
      (node (ref "D9") (pin "1") (pinfunction "A_1") (pintype "passive"))
      (node (ref "GDT1") (pin "1") (pinfunction "1_1") (pintype "passive"))
      (node (ref "GDT2") (pin "2") (pinfunction "2_2") (pintype "passive"))
      (node (ref "L2") (pin "2") (pinfunction "2_2") (pintype "passive"))
      (node (ref "OC1") (pin "2") (pinfunction "C_2") (pintype "passive"))
      (node (ref "OC2") (pin "2") (pinfunction "C_2") (pintype "passive"))
      (node (ref "OC3") (pin "2") (pinfunction "C_2") (pintype "passive"))
      (node (ref "OC4") (pin "2") (pinfunction "C_2") (pintype "passive"))
      (node (ref "OC5") (pin "2") (pinfunction "C_2") (pintype "passive"))
      (node (ref "OC6") (pin "2") (pinfunction "C_2") (pintype "passive"))
      (node (ref "OC7") (pin "2") (pinfunction "C_2") (pintype "passive"))
      (node (ref "OC8") (pin "2") (pinfunction "C_2") (pintype "passive"))
      (node (ref "U1") (pin "-VIN@1") (pinfunction "-VIN_-VIN@1") (pintype "bidirectional"))
      (node (ref "U1") (pin "-VIN@2") (pinfunction "-VIN_-VIN@2") (pintype "bidirectional"))
      (node (ref "U2") (pin "16") (pinfunction "GND2_2_16") (pintype "passive"))
      (node (ref "U2") (pin "20") (pinfunction "GND2_20") (pintype "passive"))
      (node (ref "X1") (pin "2") (pinfunction "KL_2") (pintype "passive"))
      (node (ref "X8") (pin "2") (pinfunction "KL_2") (pintype "passive"))
    )
    (net (code "38") (name "Net-(D9-AC)") (class "Default")
      (node (ref "D1") (pin "C") (pinfunction "C_C") (pintype "output"))
      (node (ref "D9") (pin "3") (pinfunction "AC_3") (pintype "passive"))
      (node (ref "OC1") (pin "1") (pinfunction "A_1") (pintype "passive"))
    )
    (net (code "39") (name "Net-(D10-AC)") (class "Default")
      (node (ref "D10") (pin "3") (pinfunction "AC_3") (pintype "passive"))
      (node (ref "D2") (pin "C") (pinfunction "C_C") (pintype "output"))
      (node (ref "OC2") (pin "1") (pinfunction "A_1") (pintype "passive"))
    )
    (net (code "40") (name "Net-(D11-AC)") (class "Default")
      (node (ref "D11") (pin "3") (pinfunction "AC_3") (pintype "passive"))
      (node (ref "D3") (pin "C") (pinfunction "C_C") (pintype "output"))
      (node (ref "OC3") (pin "1") (pinfunction "A_1") (pintype "passive"))
    )
    (net (code "41") (name "Net-(D12-AC)") (class "Default")
      (node (ref "D12") (pin "3") (pinfunction "AC_3") (pintype "passive"))
      (node (ref "D4") (pin "C") (pinfunction "C_C") (pintype "output"))
      (node (ref "OC4") (pin "1") (pinfunction "A_1") (pintype "passive"))
    )
    (net (code "42") (name "Net-(D13-AC)") (class "Default")
      (node (ref "D13") (pin "3") (pinfunction "AC_3") (pintype "passive"))
      (node (ref "D5") (pin "C") (pinfunction "C_C") (pintype "output"))
      (node (ref "OC5") (pin "1") (pinfunction "A_1") (pintype "passive"))
    )
    (net (code "43") (name "Net-(D14-AC)") (class "Default")
      (node (ref "D14") (pin "3") (pinfunction "AC_3") (pintype "passive"))
      (node (ref "D6") (pin "C") (pinfunction "C_C") (pintype "output"))
      (node (ref "OC6") (pin "1") (pinfunction "A_1") (pintype "passive"))
    )
    (net (code "44") (name "Net-(D15-AC)") (class "Default")
      (node (ref "D15") (pin "3") (pinfunction "AC_3") (pintype "passive"))
      (node (ref "D7") (pin "C") (pinfunction "C_C") (pintype "output"))
      (node (ref "OC7") (pin "1") (pinfunction "A_1") (pintype "passive"))
    )
    (net (code "45") (name "Net-(D16-AC)") (class "Default")
      (node (ref "D16") (pin "3") (pinfunction "AC_3") (pintype "passive"))
      (node (ref "D8") (pin "C") (pinfunction "C_C") (pintype "output"))
      (node (ref "OC8") (pin "1") (pinfunction "A_1") (pintype "passive"))
    )
    (net (code "46") (name "Net-(D18-AC)") (class "Default")
      (node (ref "D18") (pin "3") (pinfunction "AC_3") (pintype "passive"))
      (node (ref "D22") (pin "A") (pinfunction "A_A") (pintype "input"))
      (node (ref "OC12") (pin "4") (pinfunction "EMIT_4") (pintype "passive"))
    )
    (net (code "47") (name "Net-(D19-AC)") (class "Default")
      (node (ref "D19") (pin "3") (pinfunction "AC_3") (pintype "passive"))
      (node (ref "D23") (pin "A") (pinfunction "A_A") (pintype "input"))
      (node (ref "OC11") (pin "4") (pinfunction "EMIT_4") (pintype "passive"))
    )
    (net (code "48") (name "Net-(D20-AC)") (class "Default")
      (node (ref "D20") (pin "3") (pinfunction "AC_3") (pintype "passive"))
      (node (ref "D24") (pin "A") (pinfunction "A_A") (pintype "input"))
      (node (ref "OC10") (pin "4") (pinfunction "EMIT_4") (pintype "passive"))
    )
    (net (code "49") (name "Net-(D21-AC)") (class "Default")
      (node (ref "D21") (pin "3") (pinfunction "AC_3") (pintype "passive"))
      (node (ref "D25") (pin "A") (pinfunction "A_A") (pintype "input"))
      (node (ref "OC9") (pin "4") (pinfunction "EMIT_4") (pintype "passive"))
    )
    (net (code "50") (name "Net-(IC3-P0)") (class "Default")
      (node (ref "IC3") (pin "4") (pinfunction "P0_4") (pintype "bidirectional"))
      (node (ref "OC8") (pin "3") (pinfunction "COL_3") (pintype "passive"))
    )
    (net (code "51") (name "Net-(IC3-P1)") (class "Default")
      (node (ref "IC3") (pin "5") (pinfunction "P1_5") (pintype "bidirectional"))
      (node (ref "OC7") (pin "3") (pinfunction "COL_3") (pintype "passive"))
    )
    (net (code "52") (name "Net-(IC3-P2)") (class "Default")
      (node (ref "IC3") (pin "6") (pinfunction "P2_6") (pintype "bidirectional"))
      (node (ref "OC6") (pin "3") (pinfunction "COL_3") (pintype "passive"))
    )
    (net (code "53") (name "Net-(IC3-P3)") (class "Default")
      (node (ref "IC3") (pin "7") (pinfunction "P3_7") (pintype "bidirectional"))
      (node (ref "OC5") (pin "3") (pinfunction "COL_3") (pintype "passive"))
    )
    (net (code "54") (name "Net-(IC3-P4)") (class "Default")
      (node (ref "IC3") (pin "9") (pinfunction "P4_9") (pintype "bidirectional"))
      (node (ref "OC4") (pin "3") (pinfunction "COL_3") (pintype "passive"))
    )
    (net (code "55") (name "Net-(IC3-P5)") (class "Default")
      (node (ref "IC3") (pin "10") (pinfunction "P5_10") (pintype "bidirectional"))
      (node (ref "OC3") (pin "3") (pinfunction "COL_3") (pintype "passive"))
    )
    (net (code "56") (name "Net-(IC3-P6)") (class "Default")
      (node (ref "IC3") (pin "11") (pinfunction "P6_11") (pintype "bidirectional"))
      (node (ref "OC2") (pin "3") (pinfunction "COL_3") (pintype "passive"))
    )
    (net (code "57") (name "Net-(IC3-P7)") (class "Default")
      (node (ref "IC3") (pin "12") (pinfunction "P7_12") (pintype "bidirectional"))
      (node (ref "OC1") (pin "3") (pinfunction "COL_3") (pintype "passive"))
    )
    (net (code "58") (name "Net-(IC4-AREF)") (class "Default")
      (node (ref "C16") (pin "1") (pinfunction "1_1") (pintype "passive"))
      (node (ref "IC4") (pin "20") (pinfunction "AREF_20") (pintype "passive"))
    )
    (net (code "59") (name "Net-(IC4-PB6(XTAL1{slash}TOSC1))") (class "Default")
      (node (ref "C17") (pin "2") (pinfunction "2_2") (pintype "passive"))
      (node (ref "IC4") (pin "7") (pinfunction "PB6(XTAL1/TOSC1)_7") (pintype "bidirectional"))
      (node (ref "Q1") (pin "2") (pinfunction "2_2") (pintype "passive"))
    )
    (net (code "60") (name "Net-(IC4-PB7(XTAL2{slash}TOSC2))") (class "Default")
      (node (ref "C18") (pin "1") (pinfunction "1_1") (pintype "passive"))
      (node (ref "IC4") (pin "8") (pinfunction "PB7(XTAL2/TOSC2)_8") (pintype "bidirectional"))
      (node (ref "Q1") (pin "1") (pinfunction "1_1") (pintype "passive"))
    )
    (net (code "61") (name "Net-(IC4-PC0(ADC0))") (class "Default")
      (node (ref "IC4") (pin "23") (pinfunction "PC0(ADC0)_23") (pintype "bidirectional"))
      (node (ref "R10") (pin "2") (pinfunction "2_2") (pintype "passive"))
    )
    (net (code "62") (name "Net-(IC4-PC1(ADC1))") (class "Default")
      (node (ref "IC4") (pin "24") (pinfunction "PC1(ADC1)_24") (pintype "bidirectional"))
      (node (ref "R9") (pin "2") (pinfunction "2_2") (pintype "passive"))
    )
    (net (code "63") (name "Net-(IC4-PC2(ADC2))") (class "Default")
      (node (ref "IC4") (pin "25") (pinfunction "PC2(ADC2)_25") (pintype "bidirectional"))
      (node (ref "R2") (pin "2") (pinfunction "2_2") (pintype "passive"))
    )
    (net (code "64") (name "Net-(IC4-PC3(ADC3))") (class "Default")
      (node (ref "IC4") (pin "26") (pinfunction "PC3(ADC3)_26") (pintype "bidirectional"))
      (node (ref "R1") (pin "2") (pinfunction "2_2") (pintype "passive"))
    )
    (net (code "65") (name "Net-(IC4-PD5(T1))") (class "Default")
      (node (ref "IC4") (pin "9") (pinfunction "PD5(T1)_9") (pintype "bidirectional"))
      (node (ref "JP2") (pin "4") (pinfunction "4_4") (pintype "passive"))
    )
    (net (code "66") (name "Net-(IC4-PD6(AIN0))") (class "Default")
      (node (ref "IC4") (pin "10") (pinfunction "PD6(AIN0)_10") (pintype "bidirectional"))
      (node (ref "JP2") (pin "3") (pinfunction "3_3") (pintype "passive"))
    )
    (net (code "67") (name "Net-(IC5-VBAT)") (class "Default")
      (node (ref "G1") (pin "+") (pinfunction "+_+") (pintype "passive"))
      (node (ref "IC5") (pin "3") (pinfunction "VBAT_3") (pintype "passive"))
    )
    (net (code "68") (name "Net-(IC5-X1)") (class "Default")
      (node (ref "IC5") (pin "1") (pinfunction "X1_1") (pintype "input"))
      (node (ref "Q2") (pin "1") (pinfunction "1_1") (pintype "passive"))
    )
    (net (code "69") (name "Net-(IC5-X2)") (class "Default")
      (node (ref "IC5") (pin "2") (pinfunction "X2_2") (pintype "output"))
      (node (ref "Q2") (pin "4") (pinfunction "2_4") (pintype "passive"))
    )
    (net (code "70") (name "Net-(IC6-P1)") (class "Default")
      (node (ref "IC6") (pin "5") (pinfunction "P1_5") (pintype "bidirectional"))
      (node (ref "JP4") (pin "6") (pinfunction "6_6") (pintype "passive"))
    )
    (net (code "71") (name "Net-(IC6-P2)") (class "Default")
      (node (ref "IC6") (pin "6") (pinfunction "P2_6") (pintype "bidirectional"))
      (node (ref "JP4") (pin "7") (pinfunction "7_7") (pintype "passive"))
    )
    (net (code "72") (name "Net-(IC6-P3)") (class "Default")
      (node (ref "IC6") (pin "7") (pinfunction "P3_7") (pintype "bidirectional"))
      (node (ref "JP4") (pin "9") (pinfunction "9_9") (pintype "passive"))
    )
    (net (code "73") (name "Net-(IC6-P4)") (class "Default")
      (node (ref "IC6") (pin "9") (pinfunction "P4_9") (pintype "bidirectional"))
      (node (ref "JP4") (pin "5") (pinfunction "5_5") (pintype "passive"))
    )
    (net (code "74") (name "Net-(IC6-P5)") (class "Default")
      (node (ref "IC6") (pin "10") (pinfunction "P5_10") (pintype "bidirectional"))
      (node (ref "JP4") (pin "4") (pinfunction "4_4") (pintype "passive"))
    )
    (net (code "75") (name "Net-(IC6-P6)") (class "Default")
      (node (ref "IC6") (pin "11") (pinfunction "P6_11") (pintype "bidirectional"))
      (node (ref "JP4") (pin "3") (pinfunction "3_3") (pintype "passive"))
    )
    (net (code "76") (name "Net-(IC6-P7)") (class "Default")
      (node (ref "IC6") (pin "12") (pinfunction "P7_12") (pintype "bidirectional"))
      (node (ref "JP4") (pin "2") (pinfunction "2_2") (pintype "passive"))
    )
    (net (code "77") (name "Net-(J1-CD{slash}DAT3(~{CS}))") (class "Default")
      (node (ref "J1") (pin "DAT3") (pinfunction "CD/DAT3(~{CS})_DAT3") (pintype "bidirectional"))
      (node (ref "R7") (pin "1") (pinfunction "1_1") (pintype "passive"))
      (node (ref "R8") (pin "2") (pinfunction "2_2") (pintype "passive"))
    )
    (net (code "78") (name "Net-(J1-CLK(SCLK))") (class "Default")
      (node (ref "J1") (pin "CLK") (pinfunction "CLK(SCLK)_CLK") (pintype "bidirectional"))
      (node (ref "R3") (pin "1") (pinfunction "1_1") (pintype "passive"))
      (node (ref "R4") (pin "2") (pinfunction "2_2") (pintype "passive"))
    )
    (net (code "79") (name "Net-(J1-CMD(DI))") (class "Default")
      (node (ref "J1") (pin "CMD") (pinfunction "CMD(DI)_CMD") (pintype "bidirectional"))
      (node (ref "R5") (pin "1") (pinfunction "1_1") (pintype "passive"))
      (node (ref "R6") (pin "2") (pinfunction "2_2") (pintype "passive"))
    )
    (net (code "80") (name "Net-(JP3-Pad2)") (class "Default")
      (node (ref "JP3") (pin "2") (pinfunction "2_2") (pintype "passive"))
      (node (ref "R11") (pin "2") (pinfunction "2_2") (pintype "passive"))
      (node (ref "R13") (pin "2") (pinfunction "2_2") (pintype "passive"))
    )
    (net (code "81") (name "Net-(JP4-Pad8)") (class "Default")
      (node (ref "JP4") (pin "8") (pinfunction "8_8") (pintype "passive"))
      (node (ref "R14") (pin "1") (pinfunction "1_1") (pintype "passive"))
    )
    (net (code "82") (name "Net-(OC9-A)") (class "Default")
      (node (ref "OC9") (pin "1") (pinfunction "A_1") (pintype "passive"))
      (node (ref "R1") (pin "1") (pinfunction "1_1") (pintype "passive"))
    )
    (net (code "83") (name "Net-(OC10-A)") (class "Default")
      (node (ref "OC10") (pin "1") (pinfunction "A_1") (pintype "passive"))
      (node (ref "R2") (pin "1") (pinfunction "1_1") (pintype "passive"))
    )
    (net (code "84") (name "Net-(OC11-A)") (class "Default")
      (node (ref "OC11") (pin "1") (pinfunction "A_1") (pintype "passive"))
      (node (ref "R9") (pin "1") (pinfunction "1_1") (pintype "passive"))
    )
    (net (code "85") (name "Net-(OC12-A)") (class "Default")
      (node (ref "OC12") (pin "1") (pinfunction "A_1") (pintype "passive"))
      (node (ref "R10") (pin "1") (pinfunction "1_1") (pintype "passive"))
    )
    (net (code "86") (name "Net-(U2-GND2_3)") (class "Default")
      (node (ref "C25") (pin "2") (pinfunction "2_2") (pintype "passive"))
      (node (ref "L2") (pin "1") (pinfunction "1_1") (pintype "passive"))
      (node (ref "U2") (pin "11") (pinfunction "GND2_4_11") (pintype "passive"))
      (node (ref "U2") (pin "14") (pinfunction "GND2_3_14") (pintype "passive"))
    )
    (net (code "87") (name "Net-(U2-VISOIN)") (class "Default")
      (node (ref "C23") (pin "1") (pinfunction "1_1") (pintype "passive"))
      (node (ref "C24") (pin "1") (pinfunction "1_1") (pintype "passive"))
      (node (ref "C26") (pin "1") (pinfunction "1_1") (pintype "passive"))
      (node (ref "L1") (pin "2") (pinfunction "2_2") (pintype "passive"))
      (node (ref "U2") (pin "19") (pinfunction "VISOIN_19") (pintype "power_in"))
    )
    (net (code "88") (name "Net-(U2-VISOOUT)") (class "Default")
      (node (ref "C25") (pin "1") (pinfunction "1_1") (pintype "passive"))
      (node (ref "L1") (pin "1") (pinfunction "1_1") (pintype "passive"))
      (node (ref "U2") (pin "12") (pinfunction "VISOOUT_12") (pintype "output"))
    )
    (net (code "89") (name "Net-(X3A-KL)") (class "Default")
      (node (ref "D5") (pin "A") (pinfunction "A_A") (pintype "input"))
      (node (ref "X3") (pin "1") (pinfunction "KL_1") (pintype "passive"))
    )
    (net (code "90") (name "Net-(X3B-KL)") (class "Default")
      (node (ref "D6") (pin "A") (pinfunction "A_A") (pintype "input"))
      (node (ref "X3") (pin "2") (pinfunction "KL_2") (pintype "passive"))
    )
    (net (code "91") (name "Net-(X3C-KL)") (class "Default")
      (node (ref "D7") (pin "A") (pinfunction "A_A") (pintype "input"))
      (node (ref "X3") (pin "3") (pinfunction "KL_3") (pintype "passive"))
    )
    (net (code "92") (name "Net-(X3D-KL)") (class "Default")
      (node (ref "D8") (pin "A") (pinfunction "A_A") (pintype "input"))
      (node (ref "X3") (pin "4") (pinfunction "KL_4") (pintype "passive"))
    )
    (net (code "93") (name "Net-(X4A-KL)") (class "Default")
      (node (ref "D1") (pin "A") (pinfunction "A_A") (pintype "input"))
      (node (ref "X4") (pin "1") (pinfunction "KL_1") (pintype "passive"))
    )
    (net (code "94") (name "Net-(X4B-KL)") (class "Default")
      (node (ref "D2") (pin "A") (pinfunction "A_A") (pintype "input"))
      (node (ref "X4") (pin "2") (pinfunction "KL_2") (pintype "passive"))
    )
    (net (code "95") (name "Net-(X4C-KL)") (class "Default")
      (node (ref "D3") (pin "A") (pinfunction "A_A") (pintype "input"))
      (node (ref "X4") (pin "3") (pinfunction "KL_3") (pintype "passive"))
    )
    (net (code "96") (name "Net-(X4D-KL)") (class "Default")
      (node (ref "D4") (pin "A") (pinfunction "A_A") (pintype "input"))
      (node (ref "X4") (pin "4") (pinfunction "KL_4") (pintype "passive"))
    )
    (net (code "97") (name "Net-(X7A-KL)") (class "Default")
      (node (ref "D22") (pin "C") (pinfunction "C_C") (pintype "output"))
      (node (ref "X7") (pin "1") (pinfunction "KL_1") (pintype "passive"))
    )
    (net (code "98") (name "Net-(X7B-KL)") (class "Default")
      (node (ref "D23") (pin "C") (pinfunction "C_C") (pintype "output"))
      (node (ref "X7") (pin "2") (pinfunction "KL_2") (pintype "passive"))
    )
    (net (code "99") (name "Net-(X7C-KL)") (class "Default")
      (node (ref "D24") (pin "C") (pinfunction "C_C") (pintype "output"))
      (node (ref "X7") (pin "3") (pinfunction "KL_3") (pintype "passive"))
    )
    (net (code "100") (name "Net-(X7D-KL)") (class "Default")
      (node (ref "D25") (pin "C") (pinfunction "C_C") (pintype "output"))
      (node (ref "X7") (pin "4") (pinfunction "KL_4") (pintype "passive"))
    )
    (net (code "101") (name "Net-(X8A-KL)") (class "Default")
      (node (ref "GDT1") (pin "2") (pinfunction "2_2") (pintype "passive"))
      (node (ref "X8") (pin "1") (pinfunction "KL_1") (pintype "passive"))
      (node (ref "Z1") (pin "1") (pinfunction "1_1") (pintype "passive"))
    )
    (net (code "102") (name "Net-(X8C-KL)") (class "Default")
      (node (ref "GDT2") (pin "1") (pinfunction "1_1") (pintype "passive"))
      (node (ref "X8") (pin "3") (pinfunction "KL_3") (pintype "passive"))
      (node (ref "Z2") (pin "1") (pinfunction "1_1") (pintype "passive"))
    )
    (net (code "103") (name "unconnected-(IC4-ADC7-Pad22)") (class "Default")
      (node (ref "IC4") (pin "22") (pinfunction "ADC7_22") (pintype "bidirectional"))
    )
    (net (code "104") (name "unconnected-(IC5-SQW-Pad7)") (class "Default")
      (node (ref "IC5") (pin "7") (pinfunction "SQW_7") (pintype "open_collector"))
    )
    (net (code "105") (name "unconnected-(IC6-P0-Pad4)") (class "Default")
      (node (ref "IC6") (pin "4") (pinfunction "P0_4") (pintype "bidirectional"))
    )
    (net (code "106") (name "unconnected-(IC7-P0-Pad4)") (class "Default")
      (node (ref "IC7") (pin "4") (pinfunction "P0_4") (pintype "bidirectional"))
    )
    (net (code "107") (name "unconnected-(IC7-P1-Pad5)") (class "Default")
      (node (ref "IC7") (pin "5") (pinfunction "P1_5") (pintype "bidirectional"))
    )
    (net (code "108") (name "unconnected-(IC7-P2-Pad6)") (class "Default")
      (node (ref "IC7") (pin "6") (pinfunction "P2_6") (pintype "bidirectional"))
    )
    (net (code "109") (name "unconnected-(IC7-P3-Pad7)") (class "Default")
      (node (ref "IC7") (pin "7") (pinfunction "P3_7") (pintype "bidirectional"))
    )
    (net (code "110") (name "unconnected-(IC7-P7-Pad12)") (class "Default")
      (node (ref "IC7") (pin "12") (pinfunction "P7_12") (pintype "bidirectional"))
    )
    (net (code "111") (name "unconnected-(IC7-~{INT}-Pad13)") (class "Default")
      (node (ref "IC7") (pin "13") (pinfunction "~{INT}_13") (pintype "output"))
    )
    (net (code "112") (name "unconnected-(IC8-~{INT}-Pad13)") (class "Default")
      (node (ref "IC8") (pin "13") (pinfunction "~{INT}_13") (pintype "output"))
    )
    (net (code "113") (name "unconnected-(J1-PadDAT1)") (class "Default")
      (node (ref "J1") (pin "DAT1") (pinfunction "DAT1_DAT1") (pintype "bidirectional"))
    )
    (net (code "114") (name "unconnected-(J1-PadDAT2)") (class "Default")
      (node (ref "J1") (pin "DAT2") (pinfunction "DAT2_DAT2") (pintype "bidirectional"))
    )
    (net (code "115") (name "unconnected-(MOD1-POE+-PadP+)") (class "Default")
      (node (ref "MOD1") (pin "P+") (pinfunction "POE+_P+") (pintype "bidirectional"))
    )
    (net (code "116") (name "unconnected-(MOD1-POE--PadP-)") (class "Default")
      (node (ref "MOD1") (pin "P-") (pinfunction "POE-_P-") (pintype "bidirectional"))
    )
    (net (code "117") (name "unconnected-(U1-PadNO_CON)") (class "Default")
      (node (ref "U1") (pin "NO_CON") (pinfunction "NO_CON_NO_CON") (pintype "bidirectional"))
    )
  )
)
